# nixie-v-rev-b.net
KiCad netlist of a schematic drawn in EAGLE
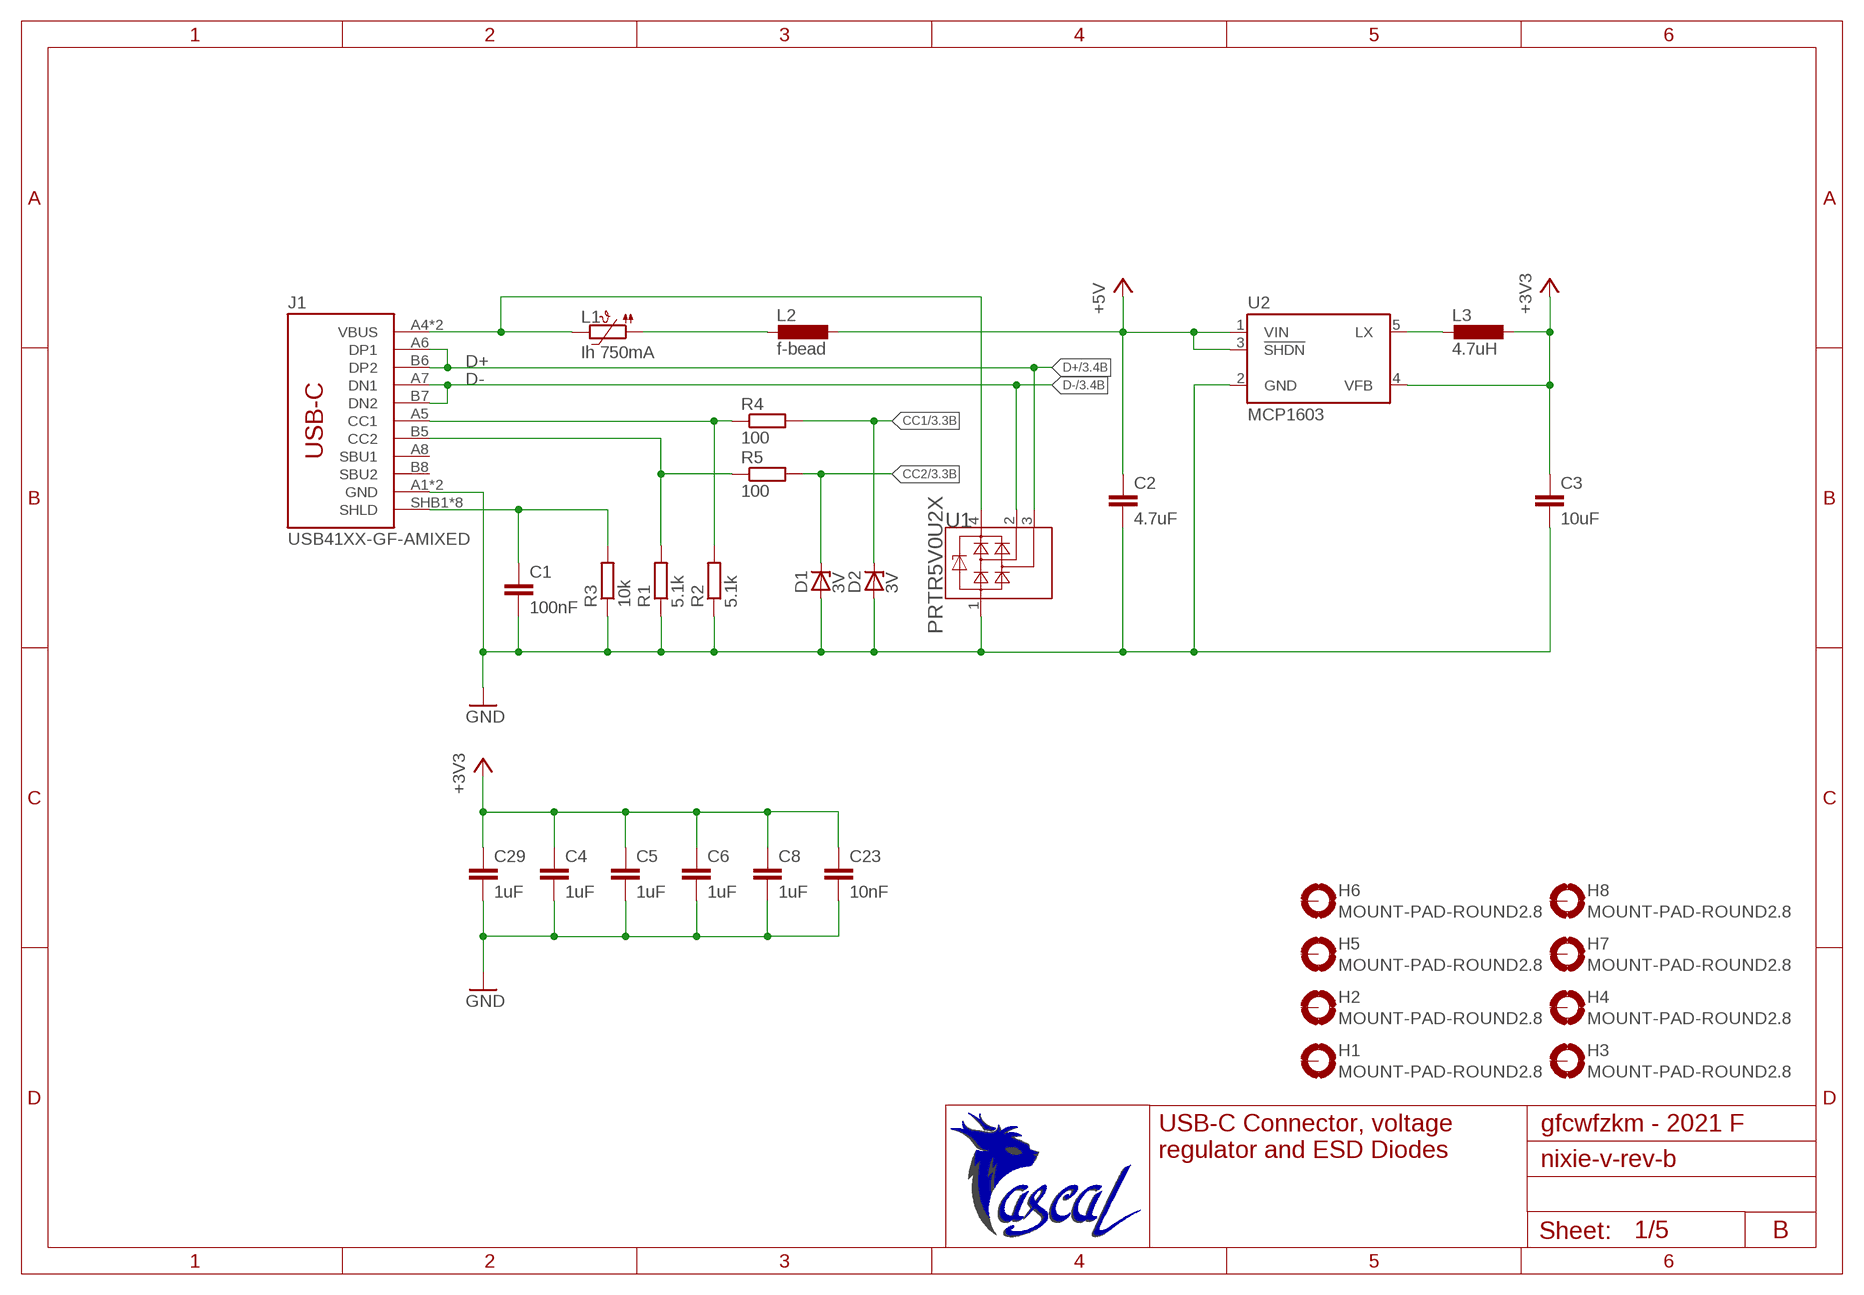
[diagram p0: schematic, sheet 1]
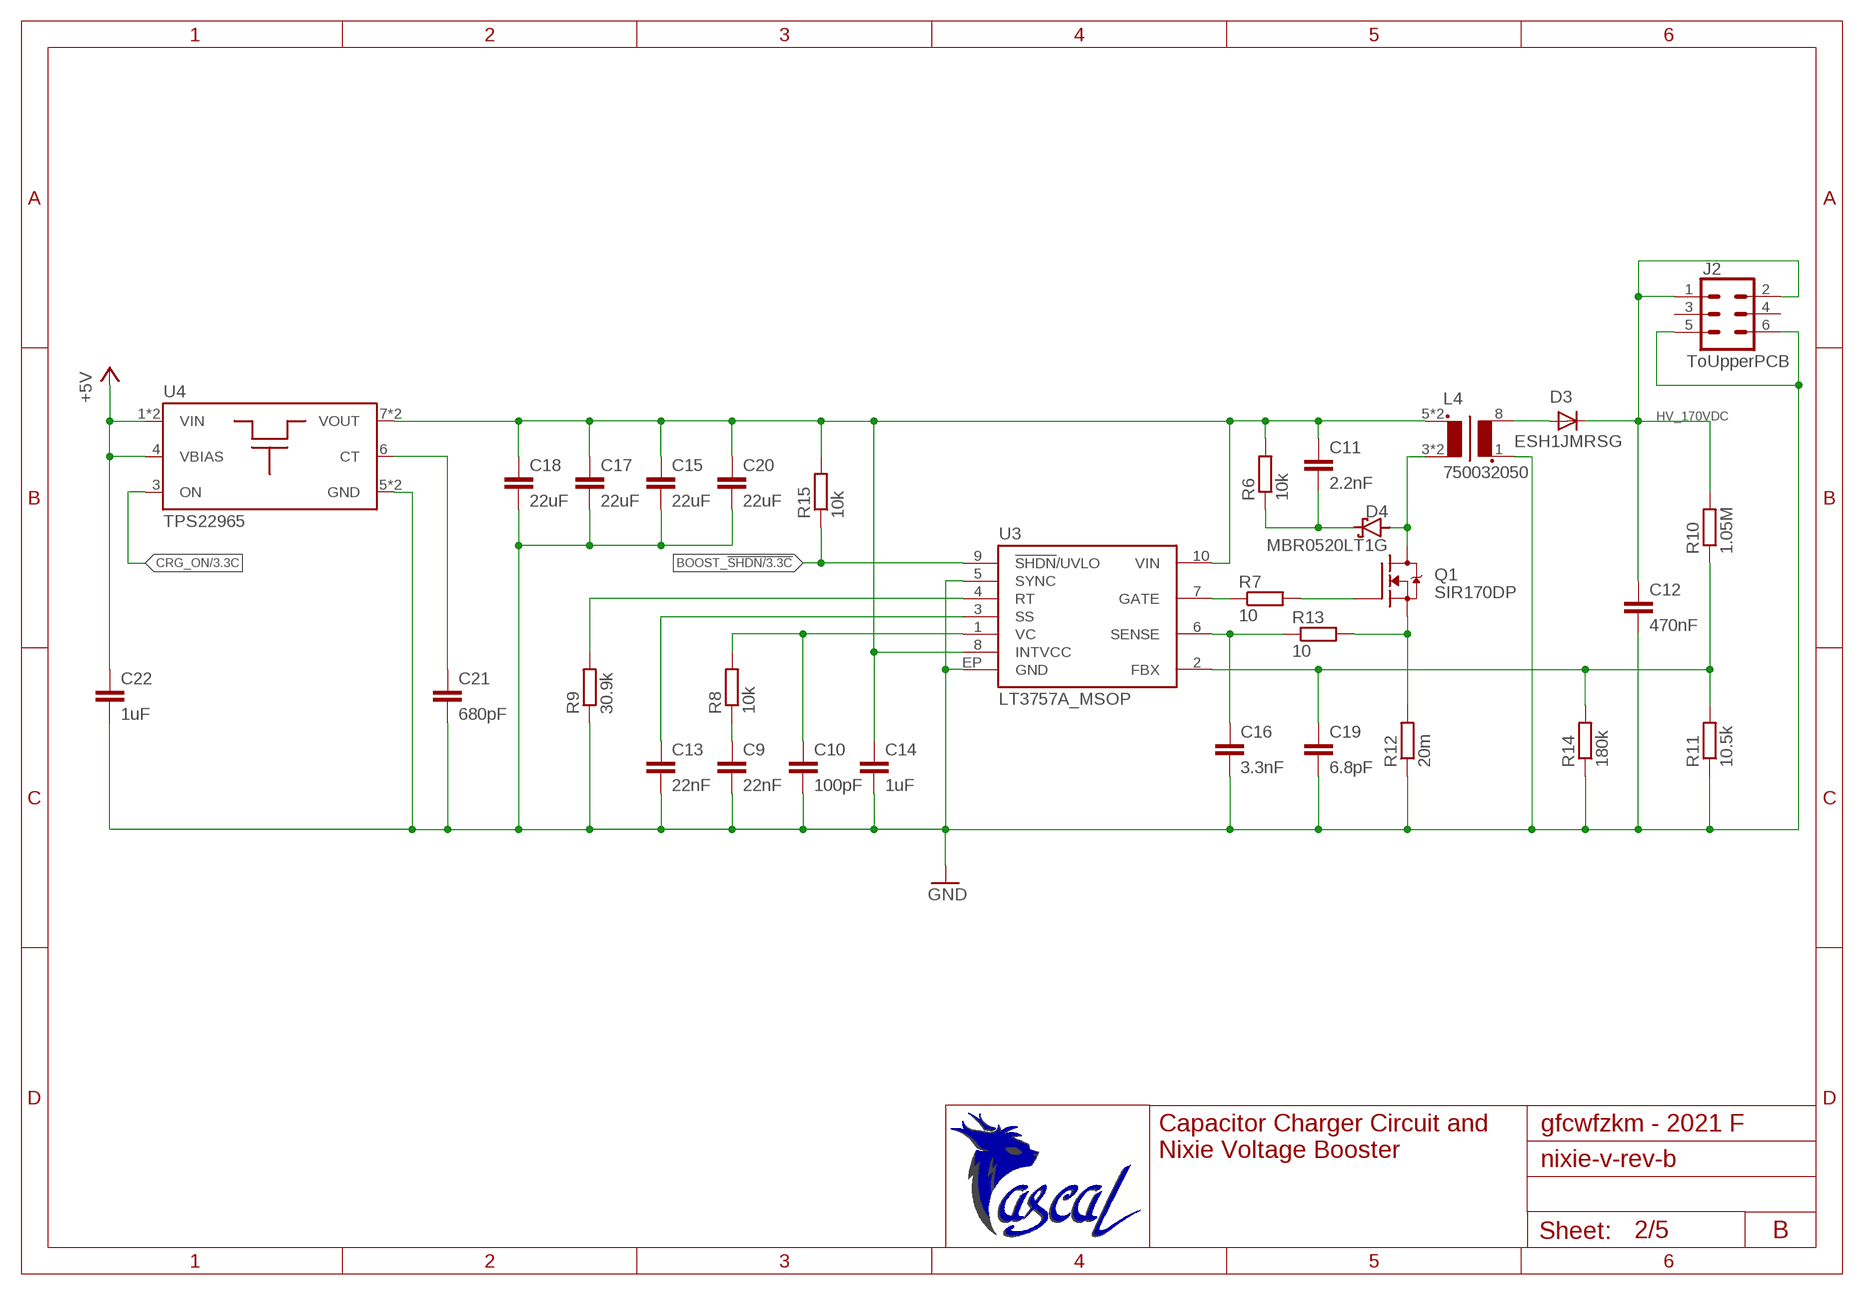
[diagram p1: schematic, sheet 2]
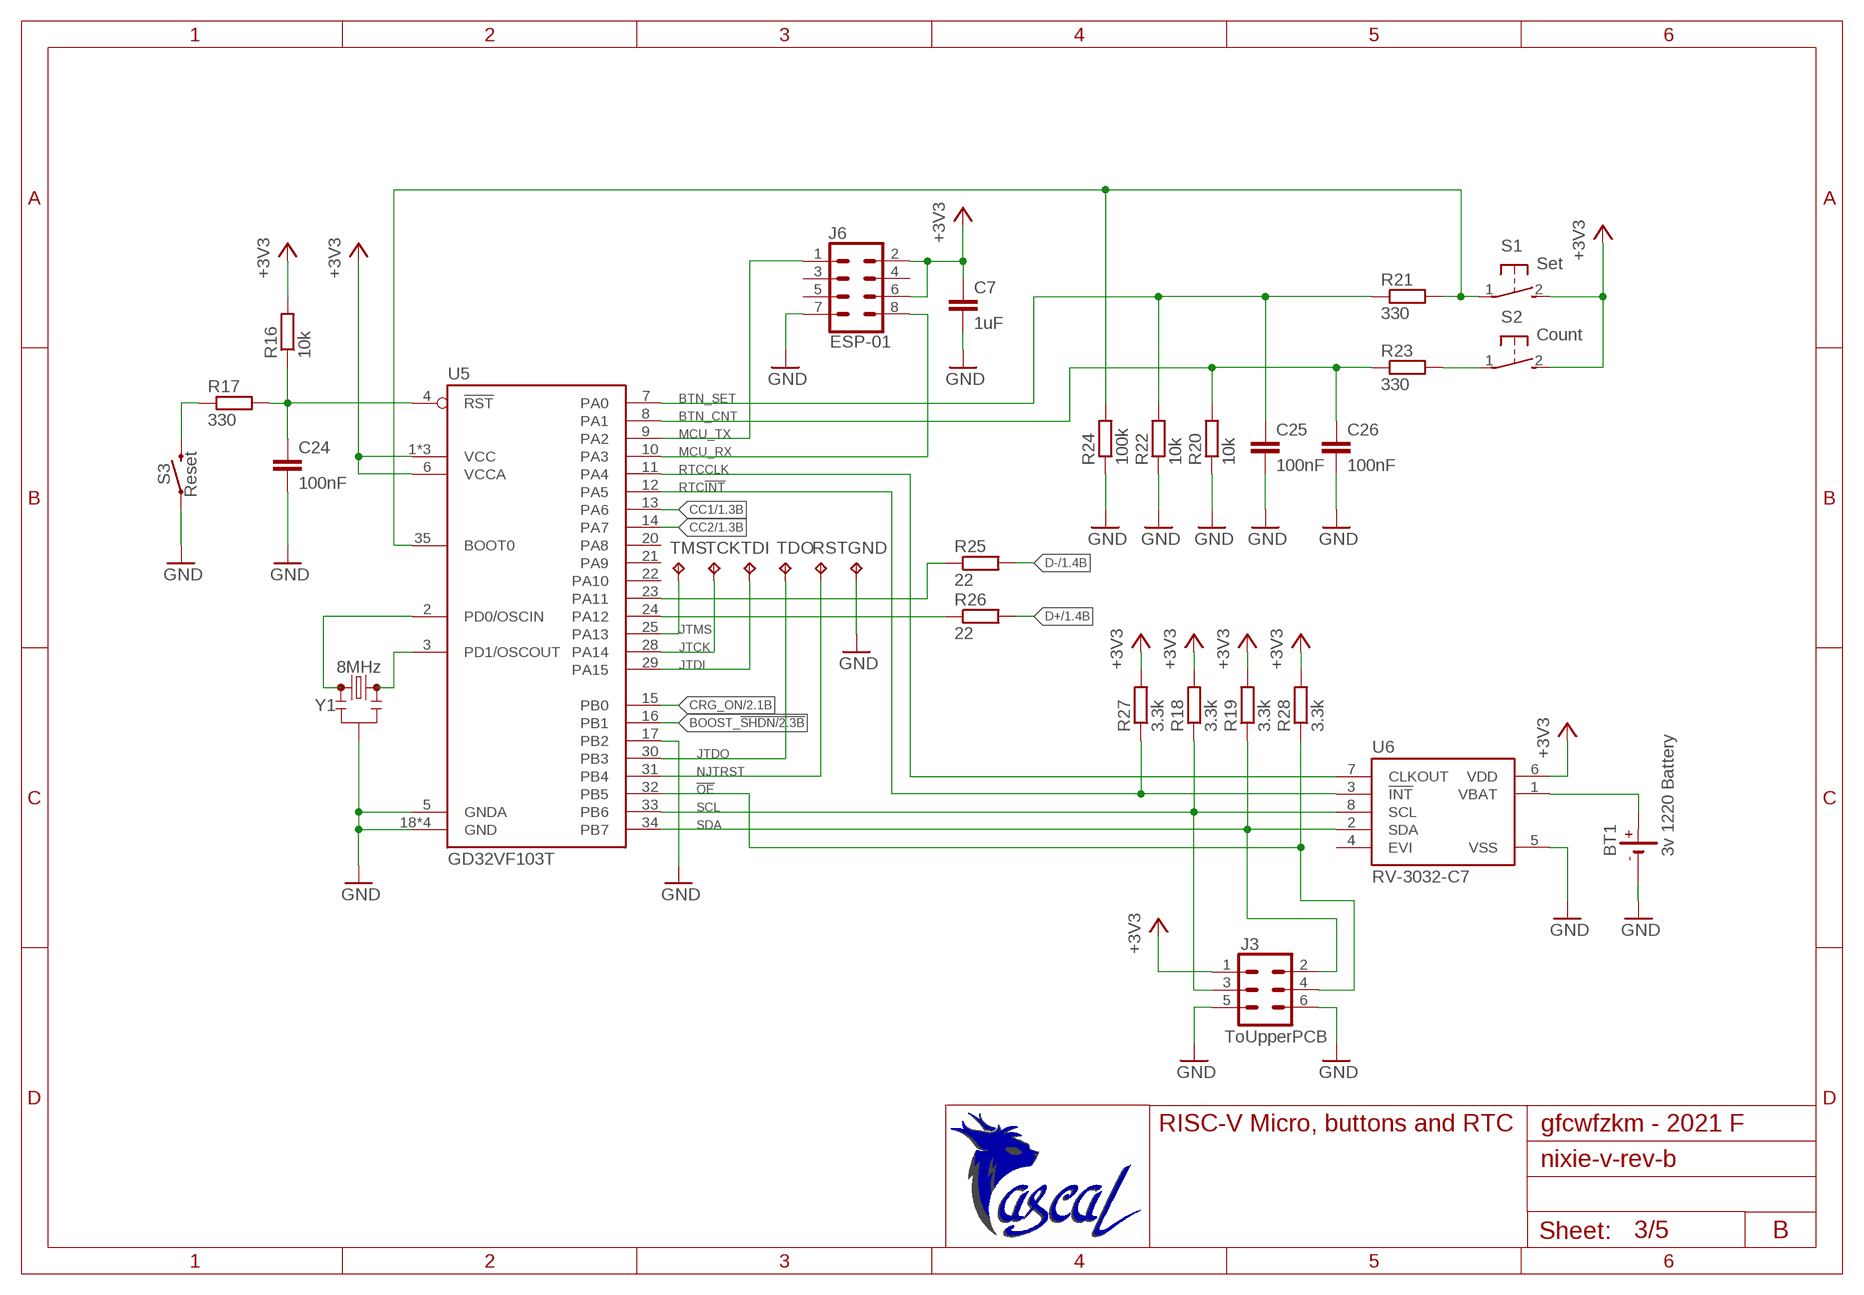
[diagram p2: schematic, sheet 3]
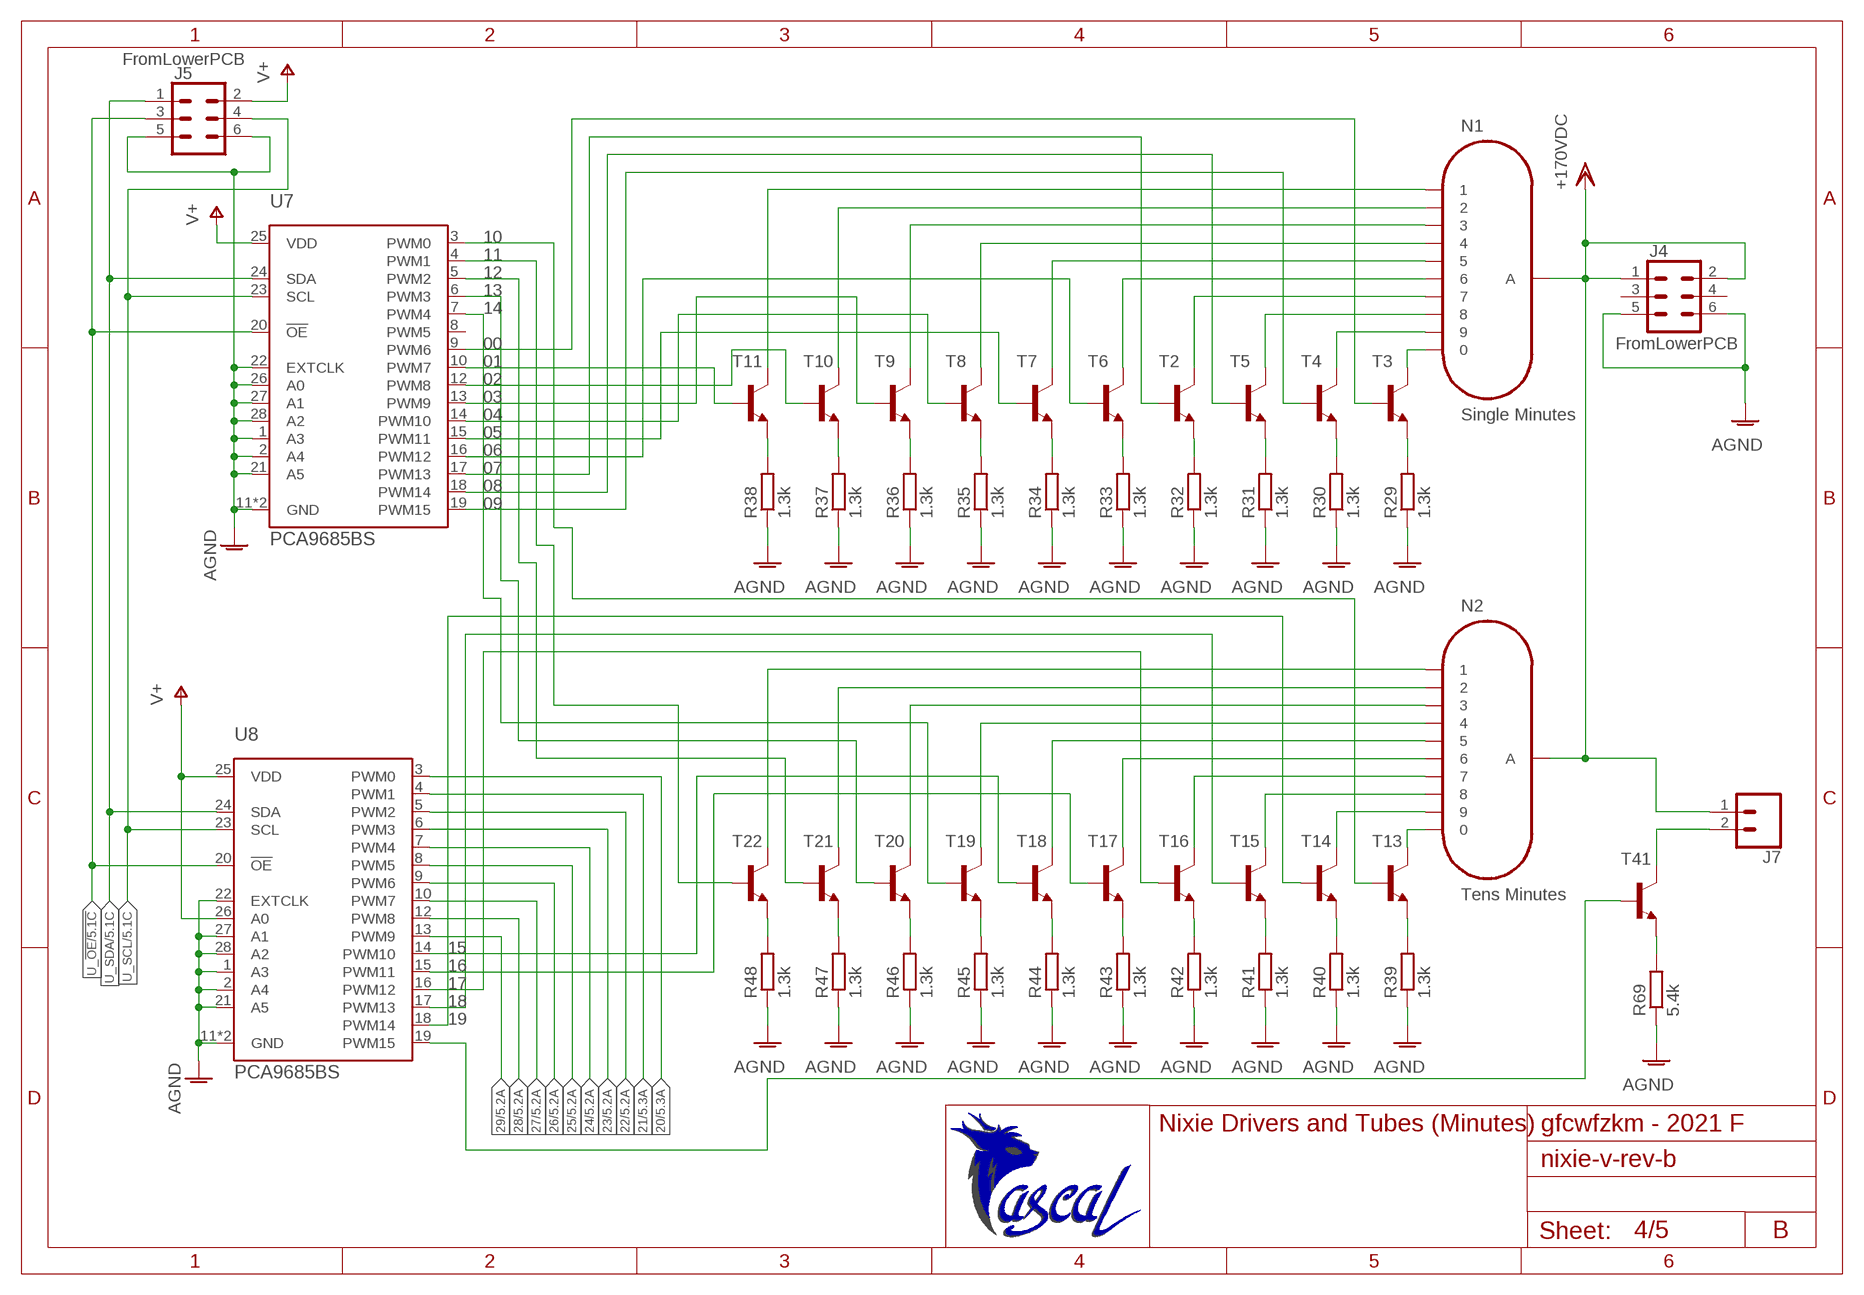
[diagram p3: schematic, sheet 4]
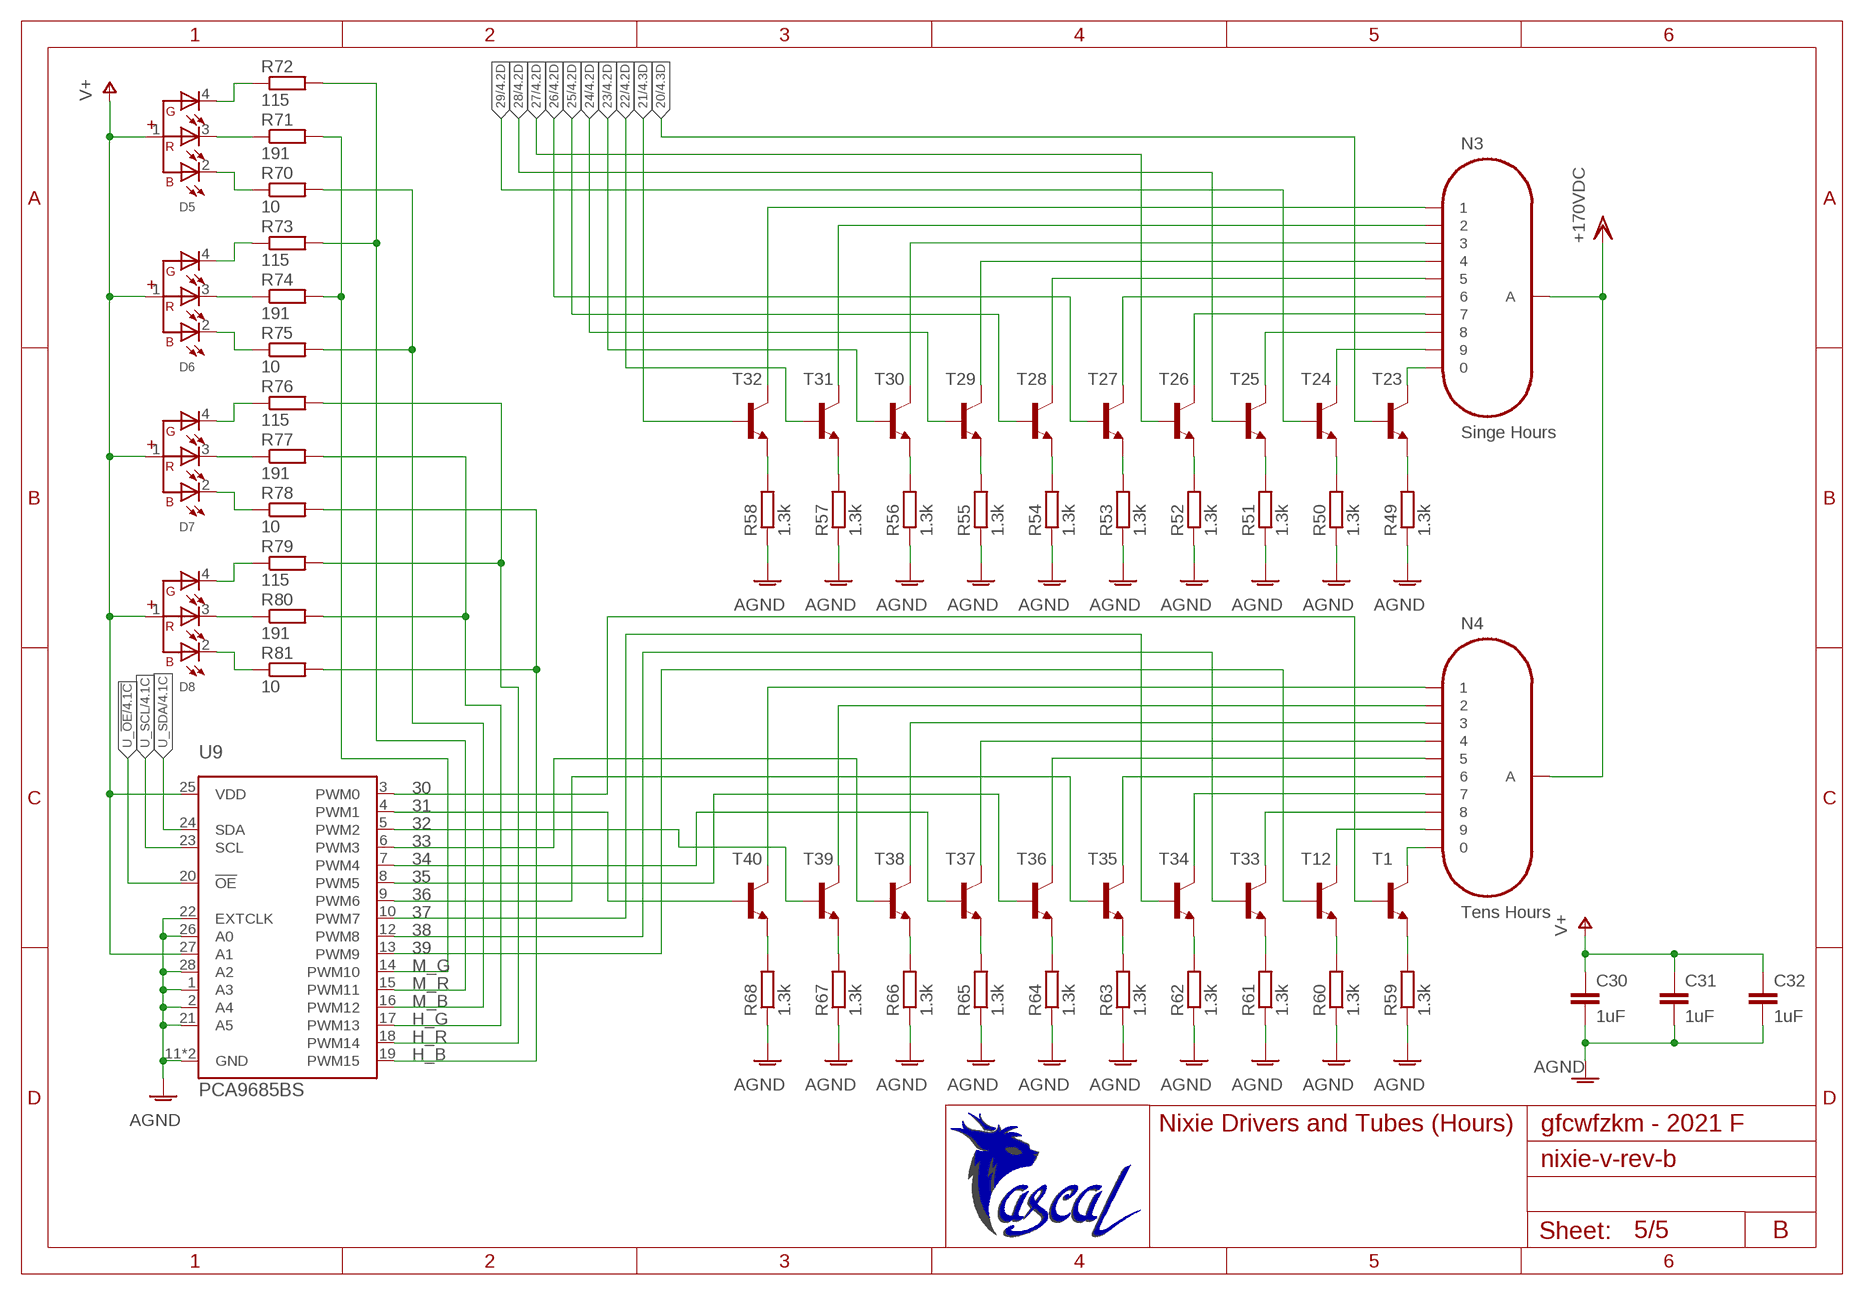
[diagram p4: schematic, sheet 5]

(export (version "E")
  (design (tool "Eeschema 10.0.6"))
  (components
    (comp (ref "J4")
      (value "FromLowerPCB")
      (footprint "eagle-import:2X3")
      (libsource (lib "eagle-import") (part "CONN_03X2FEMALE"))
    )
    (comp (ref "J5")
      (value "FromLowerPCB")
      (footprint "eagle-import:2X3")
      (libsource (lib "eagle-import") (part "CONN_03X2FEMALE"))
    )
    (comp (ref "J7")
      (value "CONN_02")
      (footprint "eagle-import:1X02")
      (libsource (lib "eagle-import") (part "CONN_02"))
    )
    (comp (ref "N1")
      (value "Single Minutes")
      (footprint "eagle-import:IN-8")
      (libsource (lib "eagle-import") (part "IN-8SMALL"))
    )
    (comp (ref "N2")
      (value "Tens Minutes")
      (footprint "eagle-import:IN-8")
      (libsource (lib "eagle-import") (part "IN-8SMALL"))
    )
    (comp (ref "R29")
      (value "1.3k")
      (footprint "eagle-import:R0603")
      (libsource (lib "eagle-import") (part "R-EU_R0603"))
    )
    (comp (ref "R30")
      (value "1.3k")
      (footprint "eagle-import:R0603")
      (libsource (lib "eagle-import") (part "R-EU_R0603"))
    )
    (comp (ref "R31")
      (value "1.3k")
      (footprint "eagle-import:R0603")
      (libsource (lib "eagle-import") (part "R-EU_R0603"))
    )
    (comp (ref "R32")
      (value "1.3k")
      (footprint "eagle-import:R0603")
      (libsource (lib "eagle-import") (part "R-EU_R0603"))
    )
    (comp (ref "R33")
      (value "1.3k")
      (footprint "eagle-import:R0603")
      (libsource (lib "eagle-import") (part "R-EU_R0603"))
    )
    (comp (ref "R34")
      (value "1.3k")
      (footprint "eagle-import:R0603")
      (libsource (lib "eagle-import") (part "R-EU_R0603"))
    )
    (comp (ref "R35")
      (value "1.3k")
      (footprint "eagle-import:R0603")
      (libsource (lib "eagle-import") (part "R-EU_R0603"))
    )
    (comp (ref "R36")
      (value "1.3k")
      (footprint "eagle-import:R0603")
      (libsource (lib "eagle-import") (part "R-EU_R0603"))
    )
    (comp (ref "R37")
      (value "1.3k")
      (footprint "eagle-import:R0603")
      (libsource (lib "eagle-import") (part "R-EU_R0603"))
    )
    (comp (ref "R38")
      (value "1.3k")
      (footprint "eagle-import:R0603")
      (libsource (lib "eagle-import") (part "R-EU_R0603"))
    )
    (comp (ref "R39")
      (value "1.3k")
      (footprint "eagle-import:R0603")
      (libsource (lib "eagle-import") (part "R-EU_R0603"))
    )
    (comp (ref "R40")
      (value "1.3k")
      (footprint "eagle-import:R0603")
      (libsource (lib "eagle-import") (part "R-EU_R0603"))
    )
    (comp (ref "R41")
      (value "1.3k")
      (footprint "eagle-import:R0603")
      (libsource (lib "eagle-import") (part "R-EU_R0603"))
    )
    (comp (ref "R42")
      (value "1.3k")
      (footprint "eagle-import:R0603")
      (libsource (lib "eagle-import") (part "R-EU_R0603"))
    )
    (comp (ref "R43")
      (value "1.3k")
      (footprint "eagle-import:R0603")
      (libsource (lib "eagle-import") (part "R-EU_R0603"))
    )
    (comp (ref "R44")
      (value "1.3k")
      (footprint "eagle-import:R0603")
      (libsource (lib "eagle-import") (part "R-EU_R0603"))
    )
    (comp (ref "R45")
      (value "1.3k")
      (footprint "eagle-import:R0603")
      (libsource (lib "eagle-import") (part "R-EU_R0603"))
    )
    (comp (ref "R46")
      (value "1.3k")
      (footprint "eagle-import:R0603")
      (libsource (lib "eagle-import") (part "R-EU_R0603"))
    )
    (comp (ref "R47")
      (value "1.3k")
      (footprint "eagle-import:R0603")
      (libsource (lib "eagle-import") (part "R-EU_R0603"))
    )
    (comp (ref "R48")
      (value "1.3k")
      (footprint "eagle-import:R0603")
      (libsource (lib "eagle-import") (part "R-EU_R0603"))
    )
    (comp (ref "R69")
      (value "5.4k")
      (footprint "eagle-import:R0603")
      (libsource (lib "eagle-import") (part "R-EU_R0603"))
    )
    (comp (ref "T2")
      (value "MSD42WT1G")
      (footprint "eagle-import:SC70-3-R")
      (libsource (lib "eagle-import") (part "MSD42WT1G"))
    )
    (comp (ref "T3")
      (value "MSD42WT1G")
      (footprint "eagle-import:SC70-3-R")
      (libsource (lib "eagle-import") (part "MSD42WT1G"))
    )
    (comp (ref "T4")
      (value "MSD42WT1G")
      (footprint "eagle-import:SC70-3-R")
      (libsource (lib "eagle-import") (part "MSD42WT1G"))
    )
    (comp (ref "T5")
      (value "MSD42WT1G")
      (footprint "eagle-import:SC70-3-R")
      (libsource (lib "eagle-import") (part "MSD42WT1G"))
    )
    (comp (ref "T6")
      (value "MSD42WT1G")
      (footprint "eagle-import:SC70-3-R")
      (libsource (lib "eagle-import") (part "MSD42WT1G"))
    )
    (comp (ref "T7")
      (value "MSD42WT1G")
      (footprint "eagle-import:SC70-3-R")
      (libsource (lib "eagle-import") (part "MSD42WT1G"))
    )
    (comp (ref "T8")
      (value "MSD42WT1G")
      (footprint "eagle-import:SC70-3-R")
      (libsource (lib "eagle-import") (part "MSD42WT1G"))
    )
    (comp (ref "T9")
      (value "MSD42WT1G")
      (footprint "eagle-import:SC70-3-R")
      (libsource (lib "eagle-import") (part "MSD42WT1G"))
    )
    (comp (ref "T10")
      (value "MSD42WT1G")
      (footprint "eagle-import:SC70-3-R")
      (libsource (lib "eagle-import") (part "MSD42WT1G"))
    )
    (comp (ref "T11")
      (value "MSD42WT1G")
      (footprint "eagle-import:SC70-3-R")
      (libsource (lib "eagle-import") (part "MSD42WT1G"))
    )
    (comp (ref "T13")
      (value "MSD42WT1G")
      (footprint "eagle-import:SC70-3-R")
      (libsource (lib "eagle-import") (part "MSD42WT1G"))
    )
    (comp (ref "T14")
      (value "MSD42WT1G")
      (footprint "eagle-import:SC70-3-R")
      (libsource (lib "eagle-import") (part "MSD42WT1G"))
    )
    (comp (ref "T15")
      (value "MSD42WT1G")
      (footprint "eagle-import:SC70-3-R")
      (libsource (lib "eagle-import") (part "MSD42WT1G"))
    )
    (comp (ref "T16")
      (value "MSD42WT1G")
      (footprint "eagle-import:SC70-3-R")
      (libsource (lib "eagle-import") (part "MSD42WT1G"))
    )
    (comp (ref "T17")
      (value "MSD42WT1G")
      (footprint "eagle-import:SC70-3-R")
      (libsource (lib "eagle-import") (part "MSD42WT1G"))
    )
    (comp (ref "T18")
      (value "MSD42WT1G")
      (footprint "eagle-import:SC70-3-R")
      (libsource (lib "eagle-import") (part "MSD42WT1G"))
    )
    (comp (ref "T19")
      (value "MSD42WT1G")
      (footprint "eagle-import:SC70-3-R")
      (libsource (lib "eagle-import") (part "MSD42WT1G"))
    )
    (comp (ref "T20")
      (value "MSD42WT1G")
      (footprint "eagle-import:SC70-3-R")
      (libsource (lib "eagle-import") (part "MSD42WT1G"))
    )
    (comp (ref "T21")
      (value "MSD42WT1G")
      (footprint "eagle-import:SC70-3-R")
      (libsource (lib "eagle-import") (part "MSD42WT1G"))
    )
    (comp (ref "T22")
      (value "MSD42WT1G")
      (footprint "eagle-import:SC70-3-R")
      (libsource (lib "eagle-import") (part "MSD42WT1G"))
    )
    (comp (ref "T41")
      (value "MSD42WT1G")
      (footprint "eagle-import:SC70-3-R")
      (libsource (lib "eagle-import") (part "MSD42WT1G"))
    )
    (comp (ref "U$4")
      (value "LOGO_PASCAL_GESELLEMPTY")
      (footprint "eagle-import:EMPTY")
      (libsource (lib "eagle-import") (part "LOGO_PASCAL_GESELLEMPTY"))
    )
    (comp (ref "U7")
      (value "PCA9685BS")
      (footprint "eagle-import:HVQFN28")
      (libsource (lib "eagle-import") (part "PCA9685BS"))
    )
    (comp (ref "U8")
      (value "PCA9685BS")
      (footprint "eagle-import:HVQFN28")
      (libsource (lib "eagle-import") (part "PCA9685BS"))
    )
    (comp (ref "C30")
      (value "1uF")
      (footprint "eagle-import:C0603")
      (libsource (lib "eagle-import") (part "C-EUC0603"))
    )
    (comp (ref "C31")
      (value "1uF")
      (footprint "eagle-import:C0603")
      (libsource (lib "eagle-import") (part "C-EUC0603"))
    )
    (comp (ref "C32")
      (value "1uF")
      (footprint "eagle-import:C0603")
      (libsource (lib "eagle-import") (part "C-EUC0603"))
    )
    (comp (ref "D5")
      (value "WL-SFRW_1206_REC_156120M173000_NOR")
      (footprint "eagle-import:WL-SFRW_1206_REC")
      (libsource (lib "eagle-import") (part "WL-SFRW_1206_REC_NOR_156120M173000"))
    )
    (comp (ref "D6")
      (value "WL-SFRW_1206_REC_156120M173000_NOR")
      (footprint "eagle-import:WL-SFRW_1206_REC")
      (libsource (lib "eagle-import") (part "WL-SFRW_1206_REC_NOR_156120M173000"))
    )
    (comp (ref "D7")
      (value "WL-SFRW_1206_REC_156120M173000_NOR")
      (footprint "eagle-import:WL-SFRW_1206_REC")
      (libsource (lib "eagle-import") (part "WL-SFRW_1206_REC_NOR_156120M173000"))
    )
    (comp (ref "D8")
      (value "WL-SFRW_1206_REC_156120M173000_NOR")
      (footprint "eagle-import:WL-SFRW_1206_REC")
      (libsource (lib "eagle-import") (part "WL-SFRW_1206_REC_NOR_156120M173000"))
    )
    (comp (ref "N3")
      (value "Singe Hours")
      (footprint "eagle-import:IN-8")
      (libsource (lib "eagle-import") (part "IN-8SMALL"))
    )
    (comp (ref "N4")
      (value "Tens Hours")
      (footprint "eagle-import:IN-8")
      (libsource (lib "eagle-import") (part "IN-8SMALL"))
    )
    (comp (ref "R49")
      (value "1.3k")
      (footprint "eagle-import:R0603")
      (libsource (lib "eagle-import") (part "R-EU_R0603"))
    )
    (comp (ref "R50")
      (value "1.3k")
      (footprint "eagle-import:R0603")
      (libsource (lib "eagle-import") (part "R-EU_R0603"))
    )
    (comp (ref "R51")
      (value "1.3k")
      (footprint "eagle-import:R0603")
      (libsource (lib "eagle-import") (part "R-EU_R0603"))
    )
    (comp (ref "R52")
      (value "1.3k")
      (footprint "eagle-import:R0603")
      (libsource (lib "eagle-import") (part "R-EU_R0603"))
    )
    (comp (ref "R53")
      (value "1.3k")
      (footprint "eagle-import:R0603")
      (libsource (lib "eagle-import") (part "R-EU_R0603"))
    )
    (comp (ref "R54")
      (value "1.3k")
      (footprint "eagle-import:R0603")
      (libsource (lib "eagle-import") (part "R-EU_R0603"))
    )
    (comp (ref "R55")
      (value "1.3k")
      (footprint "eagle-import:R0603")
      (libsource (lib "eagle-import") (part "R-EU_R0603"))
    )
    (comp (ref "R56")
      (value "1.3k")
      (footprint "eagle-import:R0603")
      (libsource (lib "eagle-import") (part "R-EU_R0603"))
    )
    (comp (ref "R57")
      (value "1.3k")
      (footprint "eagle-import:R0603")
      (libsource (lib "eagle-import") (part "R-EU_R0603"))
    )
    (comp (ref "R58")
      (value "1.3k")
      (footprint "eagle-import:R0603")
      (libsource (lib "eagle-import") (part "R-EU_R0603"))
    )
    (comp (ref "R59")
      (value "1.3k")
      (footprint "eagle-import:R0603")
      (libsource (lib "eagle-import") (part "R-EU_R0603"))
    )
    (comp (ref "R60")
      (value "1.3k")
      (footprint "eagle-import:R0603")
      (libsource (lib "eagle-import") (part "R-EU_R0603"))
    )
    (comp (ref "R61")
      (value "1.3k")
      (footprint "eagle-import:R0603")
      (libsource (lib "eagle-import") (part "R-EU_R0603"))
    )
    (comp (ref "R62")
      (value "1.3k")
      (footprint "eagle-import:R0603")
      (libsource (lib "eagle-import") (part "R-EU_R0603"))
    )
    (comp (ref "R63")
      (value "1.3k")
      (footprint "eagle-import:R0603")
      (libsource (lib "eagle-import") (part "R-EU_R0603"))
    )
    (comp (ref "R64")
      (value "1.3k")
      (footprint "eagle-import:R0603")
      (libsource (lib "eagle-import") (part "R-EU_R0603"))
    )
    (comp (ref "R65")
      (value "1.3k")
      (footprint "eagle-import:R0603")
      (libsource (lib "eagle-import") (part "R-EU_R0603"))
    )
    (comp (ref "R66")
      (value "1.3k")
      (footprint "eagle-import:R0603")
      (libsource (lib "eagle-import") (part "R-EU_R0603"))
    )
    (comp (ref "R67")
      (value "1.3k")
      (footprint "eagle-import:R0603")
      (libsource (lib "eagle-import") (part "R-EU_R0603"))
    )
    (comp (ref "R68")
      (value "1.3k")
      (footprint "eagle-import:R0603")
      (libsource (lib "eagle-import") (part "R-EU_R0603"))
    )
    (comp (ref "R70")
      (value "10")
      (footprint "eagle-import:R0603")
      (libsource (lib "eagle-import") (part "R-EU_R0603"))
    )
    (comp (ref "R71")
      (value "191")
      (footprint "eagle-import:R0603")
      (libsource (lib "eagle-import") (part "R-EU_R0603"))
    )
    (comp (ref "R72")
      (value "115")
      (footprint "eagle-import:R0603")
      (libsource (lib "eagle-import") (part "R-EU_R0603"))
    )
    (comp (ref "R73")
      (value "115")
      (footprint "eagle-import:R0603")
      (libsource (lib "eagle-import") (part "R-EU_R0603"))
    )
    (comp (ref "R74")
      (value "191")
      (footprint "eagle-import:R0603")
      (libsource (lib "eagle-import") (part "R-EU_R0603"))
    )
    (comp (ref "R75")
      (value "10")
      (footprint "eagle-import:R0603")
      (libsource (lib "eagle-import") (part "R-EU_R0603"))
    )
    (comp (ref "R76")
      (value "115")
      (footprint "eagle-import:R0603")
      (libsource (lib "eagle-import") (part "R-EU_R0603"))
    )
    (comp (ref "R77")
      (value "191")
      (footprint "eagle-import:R0603")
      (libsource (lib "eagle-import") (part "R-EU_R0603"))
    )
    (comp (ref "R78")
      (value "10")
      (footprint "eagle-import:R0603")
      (libsource (lib "eagle-import") (part "R-EU_R0603"))
    )
    (comp (ref "R79")
      (value "115")
      (footprint "eagle-import:R0603")
      (libsource (lib "eagle-import") (part "R-EU_R0603"))
    )
    (comp (ref "R80")
      (value "191")
      (footprint "eagle-import:R0603")
      (libsource (lib "eagle-import") (part "R-EU_R0603"))
    )
    (comp (ref "R81")
      (value "10")
      (footprint "eagle-import:R0603")
      (libsource (lib "eagle-import") (part "R-EU_R0603"))
    )
    (comp (ref "T1")
      (value "MSD42WT1G")
      (footprint "eagle-import:SC70-3-R")
      (libsource (lib "eagle-import") (part "MSD42WT1G"))
    )
    (comp (ref "T12")
      (value "MSD42WT1G")
      (footprint "eagle-import:SC70-3-R")
      (libsource (lib "eagle-import") (part "MSD42WT1G"))
    )
    (comp (ref "T23")
      (value "MSD42WT1G")
      (footprint "eagle-import:SC70-3-R")
      (libsource (lib "eagle-import") (part "MSD42WT1G"))
    )
    (comp (ref "T24")
      (value "MSD42WT1G")
      (footprint "eagle-import:SC70-3-R")
      (libsource (lib "eagle-import") (part "MSD42WT1G"))
    )
    (comp (ref "T25")
      (value "MSD42WT1G")
      (footprint "eagle-import:SC70-3-R")
      (libsource (lib "eagle-import") (part "MSD42WT1G"))
    )
    (comp (ref "T26")
      (value "MSD42WT1G")
      (footprint "eagle-import:SC70-3-R")
      (libsource (lib "eagle-import") (part "MSD42WT1G"))
    )
    (comp (ref "T27")
      (value "MSD42WT1G")
      (footprint "eagle-import:SC70-3-R")
      (libsource (lib "eagle-import") (part "MSD42WT1G"))
    )
    (comp (ref "T28")
      (value "MSD42WT1G")
      (footprint "eagle-import:SC70-3-R")
      (libsource (lib "eagle-import") (part "MSD42WT1G"))
    )
    (comp (ref "T29")
      (value "MSD42WT1G")
      (footprint "eagle-import:SC70-3-R")
      (libsource (lib "eagle-import") (part "MSD42WT1G"))
    )
    (comp (ref "T30")
      (value "MSD42WT1G")
      (footprint "eagle-import:SC70-3-R")
      (libsource (lib "eagle-import") (part "MSD42WT1G"))
    )
    (comp (ref "T31")
      (value "MSD42WT1G")
      (footprint "eagle-import:SC70-3-R")
      (libsource (lib "eagle-import") (part "MSD42WT1G"))
    )
    (comp (ref "T32")
      (value "MSD42WT1G")
      (footprint "eagle-import:SC70-3-R")
      (libsource (lib "eagle-import") (part "MSD42WT1G"))
    )
    (comp (ref "T33")
      (value "MSD42WT1G")
      (footprint "eagle-import:SC70-3-R")
      (libsource (lib "eagle-import") (part "MSD42WT1G"))
    )
    (comp (ref "T34")
      (value "MSD42WT1G")
      (footprint "eagle-import:SC70-3-R")
      (libsource (lib "eagle-import") (part "MSD42WT1G"))
    )
    (comp (ref "T35")
      (value "MSD42WT1G")
      (footprint "eagle-import:SC70-3-R")
      (libsource (lib "eagle-import") (part "MSD42WT1G"))
    )
    (comp (ref "T36")
      (value "MSD42WT1G")
      (footprint "eagle-import:SC70-3-R")
      (libsource (lib "eagle-import") (part "MSD42WT1G"))
    )
    (comp (ref "T37")
      (value "MSD42WT1G")
      (footprint "eagle-import:SC70-3-R")
      (libsource (lib "eagle-import") (part "MSD42WT1G"))
    )
    (comp (ref "T38")
      (value "MSD42WT1G")
      (footprint "eagle-import:SC70-3-R")
      (libsource (lib "eagle-import") (part "MSD42WT1G"))
    )
    (comp (ref "T39")
      (value "MSD42WT1G")
      (footprint "eagle-import:SC70-3-R")
      (libsource (lib "eagle-import") (part "MSD42WT1G"))
    )
    (comp (ref "T40")
      (value "MSD42WT1G")
      (footprint "eagle-import:SC70-3-R")
      (libsource (lib "eagle-import") (part "MSD42WT1G"))
    )
    (comp (ref "U$5")
      (value "LOGO_PASCAL_GESELLEMPTY")
      (footprint "eagle-import:EMPTY")
      (libsource (lib "eagle-import") (part "LOGO_PASCAL_GESELLEMPTY"))
    )
    (comp (ref "U9")
      (value "PCA9685BS")
      (footprint "eagle-import:HVQFN28")
      (libsource (lib "eagle-import") (part "PCA9685BS"))
    )
    (comp (ref "C1")
      (value "100nF")
      (footprint "eagle-import:C0603")
      (libsource (lib "eagle-import") (part "C-EUC0603"))
    )
    (comp (ref "C2")
      (value "4.7uF")
      (footprint "eagle-import:C0805")
      (libsource (lib "eagle-import") (part "C-EUC0805"))
    )
    (comp (ref "C3")
      (value "10uF")
      (footprint "eagle-import:C0805")
      (libsource (lib "eagle-import") (part "C-EUC0805"))
    )
    (comp (ref "C4")
      (value "1uF")
      (footprint "eagle-import:C0603")
      (libsource (lib "eagle-import") (part "C-EUC0603"))
    )
    (comp (ref "C5")
      (value "1uF")
      (footprint "eagle-import:C0603")
      (libsource (lib "eagle-import") (part "C-EUC0603"))
    )
    (comp (ref "C6")
      (value "1uF")
      (footprint "eagle-import:C0603")
      (libsource (lib "eagle-import") (part "C-EUC0603"))
    )
    (comp (ref "C8")
      (value "1uF")
      (footprint "eagle-import:C0603")
      (libsource (lib "eagle-import") (part "C-EUC0603"))
    )
    (comp (ref "C23")
      (value "10nF")
      (footprint "eagle-import:C0603")
      (libsource (lib "eagle-import") (part "C-EUC0603"))
    )
    (comp (ref "C29")
      (value "1uF")
      (footprint "eagle-import:C0603")
      (libsource (lib "eagle-import") (part "C-EUC0603"))
    )
    (comp (ref "D1")
      (value "3V")
      (footprint "eagle-import:SOD-523")
      (libsource (lib "eagle-import") (part "VESD05A1-02V-G3-08"))
    )
    (comp (ref "D2")
      (value "3V")
      (footprint "eagle-import:SOD-523")
      (libsource (lib "eagle-import") (part "VESD05A1-02V-G3-08"))
    )
    (comp (ref "H1")
      (value "MOUNT-PAD-ROUND2.8")
      (footprint "eagle-import:2,8-PAD")
      (libsource (lib "eagle-import") (part "MOUNT-PAD-ROUND2.8"))
    )
    (comp (ref "H2")
      (value "MOUNT-PAD-ROUND2.8")
      (footprint "eagle-import:2,8-PAD")
      (libsource (lib "eagle-import") (part "MOUNT-PAD-ROUND2.8"))
    )
    (comp (ref "H3")
      (value "MOUNT-PAD-ROUND2.8")
      (footprint "eagle-import:2,8-PAD")
      (libsource (lib "eagle-import") (part "MOUNT-PAD-ROUND2.8"))
    )
    (comp (ref "H4")
      (value "MOUNT-PAD-ROUND2.8")
      (footprint "eagle-import:2,8-PAD")
      (libsource (lib "eagle-import") (part "MOUNT-PAD-ROUND2.8"))
    )
    (comp (ref "H5")
      (value "MOUNT-PAD-ROUND2.8")
      (footprint "eagle-import:2,8-PAD")
      (libsource (lib "eagle-import") (part "MOUNT-PAD-ROUND2.8"))
    )
    (comp (ref "H6")
      (value "MOUNT-PAD-ROUND2.8")
      (footprint "eagle-import:2,8-PAD")
      (libsource (lib "eagle-import") (part "MOUNT-PAD-ROUND2.8"))
    )
    (comp (ref "H7")
      (value "MOUNT-PAD-ROUND2.8")
      (footprint "eagle-import:2,8-PAD")
      (libsource (lib "eagle-import") (part "MOUNT-PAD-ROUND2.8"))
    )
    (comp (ref "H8")
      (value "MOUNT-PAD-ROUND2.8")
      (footprint "eagle-import:2,8-PAD")
      (libsource (lib "eagle-import") (part "MOUNT-PAD-ROUND2.8"))
    )
    (comp (ref "J1")
      (value "USB41XX-GF-AMIXED")
      (footprint "eagle-import:USB4105-GF-A")
      (libsource (lib "eagle-import") (part "USB41XX-GF-AMIXED"))
    )
    (comp (ref "L1")
      (value "Ih 750mA")
      (footprint "eagle-import:R0805")
      (libsource (lib "eagle-import") (part "PTC_FUSE0805"))
    )
    (comp (ref "L2")
      (value "f-bead")
      (footprint "eagle-import:R0805")
      (libsource (lib "eagle-import") (part "L-COIL"))
    )
    (comp (ref "L3")
      (value "4.7uH")
      (footprint "eagle-import:R1210")
      (libsource (lib "eagle-import") (part "L1210"))
    )
    (comp (ref "R1")
      (value "5.1k")
      (footprint "eagle-import:R0603")
      (libsource (lib "eagle-import") (part "R-EU_R0603"))
    )
    (comp (ref "R2")
      (value "5.1k")
      (footprint "eagle-import:R0603")
      (libsource (lib "eagle-import") (part "R-EU_R0603"))
    )
    (comp (ref "R3")
      (value "10k")
      (footprint "eagle-import:R0603")
      (libsource (lib "eagle-import") (part "R-EU_R0603"))
    )
    (comp (ref "R4")
      (value "100")
      (footprint "eagle-import:R0603")
      (libsource (lib "eagle-import") (part "R-EU_R0603"))
    )
    (comp (ref "R5")
      (value "100")
      (footprint "eagle-import:R0603")
      (libsource (lib "eagle-import") (part "R-EU_R0603"))
    )
    (comp (ref "U$1")
      (value "LOGO_PASCAL_GESELL30MM")
      (footprint "eagle-import:LOGO_30MM")
      (libsource (lib "eagle-import") (part "LOGO_PASCAL_GESELL30MM"))
    )
    (comp (ref "U1")
      (value "PRTR5V0U2X")
      (footprint "eagle-import:SOT143B")
      (libsource (lib "eagle-import") (part "PRTR5V0U2X"))
    )
    (comp (ref "U2")
      (value "MCP1603")
      (footprint "eagle-import:TSOT23-5")
      (libsource (lib "eagle-import") (part "MCP1603"))
    )
    (comp (ref "C9")
      (value "22nF")
      (footprint "eagle-import:C0603")
      (libsource (lib "eagle-import") (part "C-EUC0603"))
    )
    (comp (ref "C10")
      (value "100pF")
      (footprint "eagle-import:C0603")
      (libsource (lib "eagle-import") (part "C-EUC0603"))
    )
    (comp (ref "C11")
      (value "2.2nF")
      (footprint "eagle-import:C0603")
      (libsource (lib "eagle-import") (part "C-EUC0603"))
    )
    (comp (ref "C12")
      (value "470nF")
      (footprint "eagle-import:C1812")
      (libsource (lib "eagle-import") (part "C-EUC1812"))
    )
    (comp (ref "C13")
      (value "22nF")
      (footprint "eagle-import:C0603")
      (libsource (lib "eagle-import") (part "C-EUC0603"))
    )
    (comp (ref "C14")
      (value "1uF")
      (footprint "eagle-import:C0603")
      (libsource (lib "eagle-import") (part "C-EUC0603"))
    )
    (comp (ref "C15")
      (value "22uF")
      (footprint "eagle-import:C0805")
      (libsource (lib "eagle-import") (part "C-EUC0805"))
    )
    (comp (ref "C16")
      (value "3.3nF")
      (footprint "eagle-import:C0603")
      (libsource (lib "eagle-import") (part "C-EUC0603"))
    )
    (comp (ref "C17")
      (value "22uF")
      (footprint "eagle-import:C0805")
      (libsource (lib "eagle-import") (part "C-EUC0805"))
    )
    (comp (ref "C18")
      (value "22uF")
      (footprint "eagle-import:C0805")
      (libsource (lib "eagle-import") (part "C-EUC0805"))
    )
    (comp (ref "C19")
      (value "6.8pF")
      (footprint "eagle-import:C0603")
      (libsource (lib "eagle-import") (part "C-EUC0603"))
    )
    (comp (ref "C20")
      (value "22uF")
      (footprint "eagle-import:C0805")
      (libsource (lib "eagle-import") (part "C-EUC0805"))
    )
    (comp (ref "C21")
      (value "680pF")
      (footprint "eagle-import:C0603")
      (libsource (lib "eagle-import") (part "C-EUC0603"))
    )
    (comp (ref "C22")
      (value "1uF")
      (footprint "eagle-import:C0603")
      (libsource (lib "eagle-import") (part "C-EUC0603"))
    )
    (comp (ref "D3")
      (value "ESH1JMRSG")
      (footprint "eagle-import:MICROSMA")
      (libsource (lib "eagle-import") (part "ESH1JMRSG"))
    )
    (comp (ref "D4")
      (value "MBR0520LT1G")
      (footprint "eagle-import:SOD-123")
      (fields
        (field (name "DIGIKEY_PART_NUMBER") "MBR0520LT1GOSTR-ND")
        (field (name "MANUFACTURER") "ON Semiconductor")
        (field (name "CREATED_BY") "PCBLayout.com")
      )
      (libsource (lib "eagle-import") (part "MBR0520LT1G"))
    )
    (comp (ref "J2")
      (value "ToUpperPCB")
      (footprint "eagle-import:2X3")
      (libsource (lib "eagle-import") (part "CONN_03X2FEMALE"))
    )
    (comp (ref "L4")
      (value "750032050")
      (footprint "eagle-import:750032050")
      (libsource (lib "eagle-import") (part "750032050"))
    )
    (comp (ref "Q1")
      (value "SIR170DP")
      (footprint "eagle-import:SO-08_POWERPAK")
      (libsource (lib "eagle-import") (part "SIRA36DP"))
    )
    (comp (ref "R6")
      (value "10k")
      (footprint "eagle-import:R0603")
      (libsource (lib "eagle-import") (part "R-EU_R0603"))
    )
    (comp (ref "R7")
      (value "10")
      (footprint "eagle-import:R0603")
      (libsource (lib "eagle-import") (part "R-EU_R0603"))
    )
    (comp (ref "R8")
      (value "10k")
      (footprint "eagle-import:R0603")
      (libsource (lib "eagle-import") (part "R-EU_R0603"))
    )
    (comp (ref "R9")
      (value "30.9k")
      (footprint "eagle-import:R0603")
      (libsource (lib "eagle-import") (part "R-EU_R0603"))
    )
    (comp (ref "R10")
      (value "1.05M")
      (footprint "eagle-import:R0603")
      (libsource (lib "eagle-import") (part "R-EU_R0603"))
    )
    (comp (ref "R11")
      (value "10.5k")
      (footprint "eagle-import:R0603")
      (libsource (lib "eagle-import") (part "R-EU_R0603"))
    )
    (comp (ref "R12")
      (value "20m")
      (footprint "eagle-import:R0805")
      (libsource (lib "eagle-import") (part "R-EU_R0805"))
    )
    (comp (ref "R13")
      (value "10")
      (footprint "eagle-import:R0603")
      (libsource (lib "eagle-import") (part "R-EU_R0603"))
    )
    (comp (ref "R14")
      (value "180k")
      (footprint "eagle-import:R0603")
      (libsource (lib "eagle-import") (part "R-EU_R0603"))
    )
    (comp (ref "R15")
      (value "10k")
      (footprint "eagle-import:R0603")
      (libsource (lib "eagle-import") (part "R-EU_R0603"))
    )
    (comp (ref "U$2")
      (value "LOGO_PASCAL_GESELLEMPTY")
      (footprint "eagle-import:EMPTY")
      (libsource (lib "eagle-import") (part "LOGO_PASCAL_GESELLEMPTY"))
    )
    (comp (ref "U3")
      (value "LT3757A_MSOP")
      (footprint "eagle-import:MSOP10_POWER")
      (libsource (lib "eagle-import") (part "LT3757A_MSOP"))
    )
    (comp (ref "U4")
      (value "TPS22965")
      (footprint "eagle-import:WSON-8")
      (libsource (lib "eagle-import") (part "TPS22965"))
    )
    (comp (ref "BT1")
      (value "3v 1220 Battery")
      (footprint "eagle-import:CH291-1220LF")
      (libsource (lib "eagle-import") (part "BATTERY1056_KEYSTONE"))
    )
    (comp (ref "C7")
      (value "1uF")
      (footprint "eagle-import:C0603")
      (libsource (lib "eagle-import") (part "C-EUC0603"))
    )
    (comp (ref "C24")
      (value "100nF")
      (footprint "eagle-import:C0603")
      (libsource (lib "eagle-import") (part "C-EUC0603"))
    )
    (comp (ref "C25")
      (value "100nF")
      (footprint "eagle-import:C0603")
      (libsource (lib "eagle-import") (part "C-EUC0603"))
    )
    (comp (ref "C26")
      (value "100nF")
      (footprint "eagle-import:C0603")
      (libsource (lib "eagle-import") (part "C-EUC0603"))
    )
    (comp (ref "GND")
      (value "TPB1,27")
      (footprint "eagle-import:B1,27")
      (libsource (lib "eagle-import") (part "TPB1,27"))
    )
    (comp (ref "J3")
      (value "ToUpperPCB")
      (footprint "eagle-import:2X3")
      (libsource (lib "eagle-import") (part "CONN_03X2FEMALE"))
    )
    (comp (ref "J6")
      (value "ESP-01")
      (footprint "eagle-import:2X4")
      (libsource (lib "eagle-import") (part "CONN_04X2"))
    )
    (comp (ref "R16")
      (value "10k")
      (footprint "eagle-import:R0603")
      (libsource (lib "eagle-import") (part "R-EU_R0603"))
    )
    (comp (ref "R17")
      (value "330")
      (footprint "eagle-import:R0603")
      (libsource (lib "eagle-import") (part "R-EU_R0603"))
    )
    (comp (ref "R18")
      (value "3.3k")
      (footprint "eagle-import:R0603")
      (libsource (lib "eagle-import") (part "R-EU_R0603"))
    )
    (comp (ref "R19")
      (value "3.3k")
      (footprint "eagle-import:R0603")
      (libsource (lib "eagle-import") (part "R-EU_R0603"))
    )
    (comp (ref "R20")
      (value "10k")
      (footprint "eagle-import:R0603")
      (libsource (lib "eagle-import") (part "R-EU_R0603"))
    )
    (comp (ref "R21")
      (value "330")
      (footprint "eagle-import:R0603")
      (libsource (lib "eagle-import") (part "R-EU_R0603"))
    )
    (comp (ref "R22")
      (value "10k")
      (footprint "eagle-import:R0603")
      (libsource (lib "eagle-import") (part "R-EU_R0603"))
    )
    (comp (ref "R23")
      (value "330")
      (footprint "eagle-import:R0603")
      (libsource (lib "eagle-import") (part "R-EU_R0603"))
    )
    (comp (ref "R24")
      (value "100k")
      (footprint "eagle-import:R0603")
      (libsource (lib "eagle-import") (part "R-EU_R0603"))
    )
    (comp (ref "R25")
      (value "22")
      (footprint "eagle-import:R0603")
      (libsource (lib "eagle-import") (part "R-EU_R0603"))
    )
    (comp (ref "R26")
      (value "22")
      (footprint "eagle-import:R0603")
      (libsource (lib "eagle-import") (part "R-EU_R0603"))
    )
    (comp (ref "R27")
      (value "3.3k")
      (footprint "eagle-import:R0603")
      (libsource (lib "eagle-import") (part "R-EU_R0603"))
    )
    (comp (ref "R28")
      (value "3.3k")
      (footprint "eagle-import:R0603")
      (libsource (lib "eagle-import") (part "R-EU_R0603"))
    )
    (comp (ref "RST")
      (value "TPB1,27")
      (footprint "eagle-import:B1,27")
      (libsource (lib "eagle-import") (part "TPB1,27"))
    )
    (comp (ref "S1")
      (value "Set")
      (footprint "eagle-import:B3F-31XX")
      (libsource (lib "eagle-import") (part "31-XX"))
    )
    (comp (ref "S2")
      (value "Count")
      (footprint "eagle-import:B3F-31XX")
      (libsource (lib "eagle-import") (part "31-XX"))
    )
    (comp (ref "S3")
      (value "Reset")
      (footprint "eagle-import:TACTILE_SWITCH_SMD_6.0X3.5MM")
      (libsource (lib "eagle-import") (part "MOMENTARY-SWITCH-SPST-SMD-6.0X3.5MM"))
    )
    (comp (ref "TCK")
      (value "TPB1,27")
      (footprint "eagle-import:B1,27")
      (libsource (lib "eagle-import") (part "TPB1,27"))
    )
    (comp (ref "TDI")
      (value "TPB1,27")
      (footprint "eagle-import:B1,27")
      (libsource (lib "eagle-import") (part "TPB1,27"))
    )
    (comp (ref "TDO")
      (value "TPB1,27")
      (footprint "eagle-import:B1,27")
      (libsource (lib "eagle-import") (part "TPB1,27"))
    )
    (comp (ref "TMS")
      (value "TPB1,27")
      (footprint "eagle-import:B1,27")
      (libsource (lib "eagle-import") (part "TPB1,27"))
    )
    (comp (ref "U$3")
      (value "LOGO_PASCAL_GESELLEMPTY")
      (footprint "eagle-import:EMPTY")
      (libsource (lib "eagle-import") (part "LOGO_PASCAL_GESELLEMPTY"))
    )
    (comp (ref "U5")
      (value "GD32VF103T")
      (footprint "eagle-import:QFN-36")
      (libsource (lib "eagle-import") (part "GD32VF103T"))
    )
    (comp (ref "U6")
      (value "RV-3032-C7")
      (footprint "eagle-import:RV-3028-C7")
      (libsource (lib "eagle-import") (part "RV-3032-C7"))
    )
    (comp (ref "Y1")
      (value "8MHz")
      (footprint "eagle-import:RESONATOR-SMD-3.2X1.3")
      (libsource (lib "eagle-import") (part "RESONATOR-8MHZSMD_3.2X1.3"))
    )
  )
  (nets
    (net (code "1") (name "+3V3") (class "Default")
      (node (ref "C23") (pin "1") (pinfunction "1_1") (pintype "passive"))
      (node (ref "C29") (pin "1") (pinfunction "1_1") (pintype "passive"))
      (node (ref "C3") (pin "1") (pinfunction "1_1") (pintype "passive"))
      (node (ref "C4") (pin "1") (pinfunction "1_1") (pintype "passive"))
      (node (ref "C5") (pin "1") (pinfunction "1_1") (pintype "passive"))
      (node (ref "C6") (pin "1") (pinfunction "1_1") (pintype "passive"))
      (node (ref "C7") (pin "1") (pinfunction "1_1") (pintype "passive"))
      (node (ref "C8") (pin "1") (pinfunction "1_1") (pintype "passive"))
      (node (ref "J3") (pin "1") (pinfunction "1_1") (pintype "bidirectional"))
      (node (ref "J6") (pin "2") (pinfunction "2_2") (pintype "passive"))
      (node (ref "J6") (pin "6") (pinfunction "6_6") (pintype "passive"))
      (node (ref "L3") (pin "1") (pinfunction "1_1") (pintype "passive"))
      (node (ref "R16") (pin "2") (pinfunction "2_2") (pintype "passive"))
      (node (ref "R18") (pin "2") (pinfunction "2_2") (pintype "passive"))
      (node (ref "R19") (pin "2") (pinfunction "2_2") (pintype "passive"))
      (node (ref "R27") (pin "2") (pinfunction "2_2") (pintype "passive"))
      (node (ref "R28") (pin "2") (pinfunction "2_2") (pintype "passive"))
      (node (ref "S1") (pin "2") (pinfunction "S_2") (pintype "passive"))
      (node (ref "S2") (pin "2") (pinfunction "S_2") (pintype "passive"))
      (node (ref "U2") (pin "4") (pinfunction "VFB_4") (pintype "power_in"))
      (node (ref "U5") (pin "1") (pinfunction "VCC_1") (pintype "power_in"))
      (node (ref "U5") (pin "19") (pinfunction "VCC_19") (pintype "power_in"))
      (node (ref "U5") (pin "27") (pinfunction "VCC_27") (pintype "power_in"))
      (node (ref "U5") (pin "6") (pinfunction "VCCA_6") (pintype "power_in"))
      (node (ref "U6") (pin "6") (pinfunction "VDD_6") (pintype "bidirectional"))
    )
    (net (code "2") (name "+5V") (class "Default")
      (node (ref "C2") (pin "1") (pinfunction "1_1") (pintype "passive"))
      (node (ref "C22") (pin "1") (pinfunction "1_1") (pintype "passive"))
      (node (ref "L2") (pin "1") (pinfunction "1_1") (pintype "passive"))
      (node (ref "U2") (pin "1") (pinfunction "VIN_1") (pintype "power_in"))
      (node (ref "U2") (pin "3") (pinfunction "~{SHDN}_3") (pintype "power_in"))
      (node (ref "U4") (pin "1") (pinfunction "VIN_1") (pintype "input"))
      (node (ref "U4") (pin "2") (pinfunction "VIN_2") (pintype "input"))
      (node (ref "U4") (pin "4") (pinfunction "VBIAS_4") (pintype "power_in"))
    )
    (net (code "3") (name "+170VDC") (class "Default")
      (node (ref "J4") (pin "1") (pinfunction "1_1") (pintype "bidirectional"))
      (node (ref "J4") (pin "2") (pinfunction "2_2") (pintype "bidirectional"))
      (node (ref "J7") (pin "1") (pinfunction "1_1") (pintype "passive"))
      (node (ref "N1") (pin "A") (pinfunction "A_A") (pintype "power_in"))
      (node (ref "N2") (pin "A") (pinfunction "A_A") (pintype "power_in"))
      (node (ref "N3") (pin "A") (pinfunction "A_A") (pintype "power_in"))
      (node (ref "N4") (pin "A") (pinfunction "A_A") (pintype "power_in"))
    )
    (net (code "4") (name "00") (class "Default")
      (node (ref "T3") (pin "1") (pinfunction "B_1") (pintype "passive"))
      (node (ref "U7") (pin "9") (pinfunction "PWM6_9") (pintype "output"))
    )
    (net (code "5") (name "01") (class "Default")
      (node (ref "T11") (pin "1") (pinfunction "B_1") (pintype "passive"))
      (node (ref "U7") (pin "10") (pinfunction "PWM7_10") (pintype "output"))
    )
    (net (code "6") (name "02") (class "Default")
      (node (ref "T10") (pin "1") (pinfunction "B_1") (pintype "passive"))
      (node (ref "U7") (pin "12") (pinfunction "PWM8_12") (pintype "output"))
    )
    (net (code "7") (name "03") (class "Default")
      (node (ref "T9") (pin "1") (pinfunction "B_1") (pintype "passive"))
      (node (ref "U7") (pin "13") (pinfunction "PWM9_13") (pintype "output"))
    )
    (net (code "8") (name "04") (class "Default")
      (node (ref "T8") (pin "1") (pinfunction "B_1") (pintype "passive"))
      (node (ref "U7") (pin "14") (pinfunction "PWM10_14") (pintype "output"))
    )
    (net (code "9") (name "05") (class "Default")
      (node (ref "T7") (pin "1") (pinfunction "B_1") (pintype "passive"))
      (node (ref "U7") (pin "15") (pinfunction "PWM11_15") (pintype "output"))
    )
    (net (code "10") (name "06") (class "Default")
      (node (ref "T6") (pin "1") (pinfunction "B_1") (pintype "passive"))
      (node (ref "U7") (pin "16") (pinfunction "PWM12_16") (pintype "output"))
    )
    (net (code "11") (name "07") (class "Default")
      (node (ref "T2") (pin "1") (pinfunction "B_1") (pintype "passive"))
      (node (ref "U7") (pin "17") (pinfunction "PWM13_17") (pintype "output"))
    )
    (net (code "12") (name "08") (class "Default")
      (node (ref "T5") (pin "1") (pinfunction "B_1") (pintype "passive"))
      (node (ref "U7") (pin "18") (pinfunction "PWM14_18") (pintype "output"))
    )
    (net (code "13") (name "09") (class "Default")
      (node (ref "T4") (pin "1") (pinfunction "B_1") (pintype "passive"))
      (node (ref "U7") (pin "19") (pinfunction "PWM15_19") (pintype "output"))
    )
    (net (code "14") (name "10") (class "Default")
      (node (ref "T13") (pin "1") (pinfunction "B_1") (pintype "passive"))
      (node (ref "U7") (pin "3") (pinfunction "PWM0_3") (pintype "output"))
    )
    (net (code "15") (name "11") (class "Default")
      (node (ref "T22") (pin "1") (pinfunction "B_1") (pintype "passive"))
      (node (ref "U7") (pin "4") (pinfunction "PWM1_4") (pintype "output"))
    )
    (net (code "16") (name "12") (class "Default")
      (node (ref "T21") (pin "1") (pinfunction "B_1") (pintype "passive"))
      (node (ref "U7") (pin "5") (pinfunction "PWM2_5") (pintype "output"))
    )
    (net (code "17") (name "13") (class "Default")
      (node (ref "T20") (pin "1") (pinfunction "B_1") (pintype "passive"))
      (node (ref "U7") (pin "6") (pinfunction "PWM3_6") (pintype "output"))
    )
    (net (code "18") (name "14") (class "Default")
      (node (ref "T19") (pin "1") (pinfunction "B_1") (pintype "passive"))
      (node (ref "U7") (pin "7") (pinfunction "PWM4_7") (pintype "output"))
    )
    (net (code "19") (name "15") (class "Default")
      (node (ref "T18") (pin "1") (pinfunction "B_1") (pintype "passive"))
      (node (ref "U8") (pin "14") (pinfunction "PWM10_14") (pintype "output"))
    )
    (net (code "20") (name "16") (class "Default")
      (node (ref "T17") (pin "1") (pinfunction "B_1") (pintype "passive"))
      (node (ref "U8") (pin "15") (pinfunction "PWM11_15") (pintype "output"))
    )
    (net (code "21") (name "17") (class "Default")
      (node (ref "T16") (pin "1") (pinfunction "B_1") (pintype "passive"))
      (node (ref "U8") (pin "16") (pinfunction "PWM12_16") (pintype "output"))
    )
    (net (code "22") (name "18") (class "Default")
      (node (ref "T15") (pin "1") (pinfunction "B_1") (pintype "passive"))
      (node (ref "U8") (pin "17") (pinfunction "PWM13_17") (pintype "output"))
    )
    (net (code "23") (name "19") (class "Default")
      (node (ref "T14") (pin "1") (pinfunction "B_1") (pintype "passive"))
      (node (ref "U8") (pin "18") (pinfunction "PWM14_18") (pintype "output"))
    )
    (net (code "24") (name "20") (class "Default")
      (node (ref "T23") (pin "1") (pinfunction "B_1") (pintype "passive"))
      (node (ref "U8") (pin "3") (pinfunction "PWM0_3") (pintype "output"))
    )
    (net (code "25") (name "21") (class "Default")
      (node (ref "T32") (pin "1") (pinfunction "B_1") (pintype "passive"))
      (node (ref "U8") (pin "4") (pinfunction "PWM1_4") (pintype "output"))
    )
    (net (code "26") (name "22") (class "Default")
      (node (ref "T31") (pin "1") (pinfunction "B_1") (pintype "passive"))
      (node (ref "U8") (pin "5") (pinfunction "PWM2_5") (pintype "output"))
    )
    (net (code "27") (name "23") (class "Default")
      (node (ref "T30") (pin "1") (pinfunction "B_1") (pintype "passive"))
      (node (ref "U8") (pin "6") (pinfunction "PWM3_6") (pintype "output"))
    )
    (net (code "28") (name "24") (class "Default")
      (node (ref "T29") (pin "1") (pinfunction "B_1") (pintype "passive"))
      (node (ref "U8") (pin "7") (pinfunction "PWM4_7") (pintype "output"))
    )
    (net (code "29") (name "25") (class "Default")
      (node (ref "T28") (pin "1") (pinfunction "B_1") (pintype "passive"))
      (node (ref "U8") (pin "8") (pinfunction "PWM5_8") (pintype "output"))
    )
    (net (code "30") (name "26") (class "Default")
      (node (ref "T27") (pin "1") (pinfunction "B_1") (pintype "passive"))
      (node (ref "U8") (pin "9") (pinfunction "PWM6_9") (pintype "output"))
    )
    (net (code "31") (name "27") (class "Default")
      (node (ref "T26") (pin "1") (pinfunction "B_1") (pintype "passive"))
      (node (ref "U8") (pin "10") (pinfunction "PWM7_10") (pintype "output"))
    )
    (net (code "32") (name "28") (class "Default")
      (node (ref "T25") (pin "1") (pinfunction "B_1") (pintype "passive"))
      (node (ref "U8") (pin "12") (pinfunction "PWM8_12") (pintype "output"))
    )
    (net (code "33") (name "29") (class "Default")
      (node (ref "T24") (pin "1") (pinfunction "B_1") (pintype "passive"))
      (node (ref "U8") (pin "13") (pinfunction "PWM9_13") (pintype "output"))
    )
    (net (code "34") (name "30") (class "Default")
      (node (ref "T1") (pin "1") (pinfunction "B_1") (pintype "passive"))
      (node (ref "U9") (pin "3") (pinfunction "PWM0_3") (pintype "output"))
    )
    (net (code "35") (name "31") (class "Default")
      (node (ref "T40") (pin "1") (pinfunction "B_1") (pintype "passive"))
      (node (ref "U9") (pin "4") (pinfunction "PWM1_4") (pintype "output"))
    )
    (net (code "36") (name "32") (class "Default")
      (node (ref "T39") (pin "1") (pinfunction "B_1") (pintype "passive"))
      (node (ref "U9") (pin "5") (pinfunction "PWM2_5") (pintype "output"))
    )
    (net (code "37") (name "33") (class "Default")
      (node (ref "T38") (pin "1") (pinfunction "B_1") (pintype "passive"))
      (node (ref "U9") (pin "6") (pinfunction "PWM3_6") (pintype "output"))
    )
    (net (code "38") (name "34") (class "Default")
      (node (ref "T37") (pin "1") (pinfunction "B_1") (pintype "passive"))
      (node (ref "U9") (pin "7") (pinfunction "PWM4_7") (pintype "output"))
    )
    (net (code "39") (name "35") (class "Default")
      (node (ref "T36") (pin "1") (pinfunction "B_1") (pintype "passive"))
      (node (ref "U9") (pin "8") (pinfunction "PWM5_8") (pintype "output"))
    )
    (net (code "40") (name "36") (class "Default")
      (node (ref "T35") (pin "1") (pinfunction "B_1") (pintype "passive"))
      (node (ref "U9") (pin "9") (pinfunction "PWM6_9") (pintype "output"))
    )
    (net (code "41") (name "37") (class "Default")
      (node (ref "T34") (pin "1") (pinfunction "B_1") (pintype "passive"))
      (node (ref "U9") (pin "10") (pinfunction "PWM7_10") (pintype "output"))
    )
    (net (code "42") (name "38") (class "Default")
      (node (ref "T33") (pin "1") (pinfunction "B_1") (pintype "passive"))
      (node (ref "U9") (pin "12") (pinfunction "PWM8_12") (pintype "output"))
    )
    (net (code "43") (name "39") (class "Default")
      (node (ref "T12") (pin "1") (pinfunction "B_1") (pintype "passive"))
      (node (ref "U9") (pin "13") (pinfunction "PWM9_13") (pintype "output"))
    )
    (net (code "44") (name "AGND") (class "Default")
      (node (ref "C30") (pin "2") (pinfunction "2_2") (pintype "passive"))
      (node (ref "C31") (pin "2") (pinfunction "2_2") (pintype "passive"))
      (node (ref "C32") (pin "2") (pinfunction "2_2") (pintype "passive"))
      (node (ref "J4") (pin "5") (pinfunction "5_5") (pintype "bidirectional"))
      (node (ref "J4") (pin "6") (pinfunction "6_6") (pintype "bidirectional"))
      (node (ref "J5") (pin "5") (pinfunction "5_5") (pintype "bidirectional"))
      (node (ref "J5") (pin "6") (pinfunction "6_6") (pintype "bidirectional"))
      (node (ref "R29") (pin "1") (pinfunction "1_1") (pintype "passive"))
      (node (ref "R30") (pin "1") (pinfunction "1_1") (pintype "passive"))
      (node (ref "R31") (pin "1") (pinfunction "1_1") (pintype "passive"))
      (node (ref "R32") (pin "1") (pinfunction "1_1") (pintype "passive"))
      (node (ref "R33") (pin "1") (pinfunction "1_1") (pintype "passive"))
      (node (ref "R34") (pin "1") (pinfunction "1_1") (pintype "passive"))
      (node (ref "R35") (pin "1") (pinfunction "1_1") (pintype "passive"))
      (node (ref "R36") (pin "1") (pinfunction "1_1") (pintype "passive"))
      (node (ref "R37") (pin "1") (pinfunction "1_1") (pintype "passive"))
      (node (ref "R38") (pin "1") (pinfunction "1_1") (pintype "passive"))
      (node (ref "R39") (pin "1") (pinfunction "1_1") (pintype "passive"))
      (node (ref "R40") (pin "1") (pinfunction "1_1") (pintype "passive"))
      (node (ref "R41") (pin "1") (pinfunction "1_1") (pintype "passive"))
      (node (ref "R42") (pin "1") (pinfunction "1_1") (pintype "passive"))
      (node (ref "R43") (pin "1") (pinfunction "1_1") (pintype "passive"))
      (node (ref "R44") (pin "1") (pinfunction "1_1") (pintype "passive"))
      (node (ref "R45") (pin "1") (pinfunction "1_1") (pintype "passive"))
      (node (ref "R46") (pin "1") (pinfunction "1_1") (pintype "passive"))
      (node (ref "R47") (pin "1") (pinfunction "1_1") (pintype "passive"))
      (node (ref "R48") (pin "1") (pinfunction "1_1") (pintype "passive"))
      (node (ref "R49") (pin "1") (pinfunction "1_1") (pintype "passive"))
      (node (ref "R50") (pin "1") (pinfunction "1_1") (pintype "passive"))
      (node (ref "R51") (pin "1") (pinfunction "1_1") (pintype "passive"))
      (node (ref "R52") (pin "1") (pinfunction "1_1") (pintype "passive"))
      (node (ref "R53") (pin "1") (pinfunction "1_1") (pintype "passive"))
      (node (ref "R54") (pin "1") (pinfunction "1_1") (pintype "passive"))
      (node (ref "R55") (pin "1") (pinfunction "1_1") (pintype "passive"))
      (node (ref "R56") (pin "1") (pinfunction "1_1") (pintype "passive"))
      (node (ref "R57") (pin "1") (pinfunction "1_1") (pintype "passive"))
      (node (ref "R58") (pin "1") (pinfunction "1_1") (pintype "passive"))
      (node (ref "R59") (pin "1") (pinfunction "1_1") (pintype "passive"))
      (node (ref "R60") (pin "1") (pinfunction "1_1") (pintype "passive"))
      (node (ref "R61") (pin "1") (pinfunction "1_1") (pintype "passive"))
      (node (ref "R62") (pin "1") (pinfunction "1_1") (pintype "passive"))
      (node (ref "R63") (pin "1") (pinfunction "1_1") (pintype "passive"))
      (node (ref "R64") (pin "1") (pinfunction "1_1") (pintype "passive"))
      (node (ref "R65") (pin "1") (pinfunction "1_1") (pintype "passive"))
      (node (ref "R66") (pin "1") (pinfunction "1_1") (pintype "passive"))
      (node (ref "R67") (pin "1") (pinfunction "1_1") (pintype "passive"))
      (node (ref "R68") (pin "1") (pinfunction "1_1") (pintype "passive"))
      (node (ref "R69") (pin "1") (pinfunction "1_1") (pintype "passive"))
      (node (ref "U7") (pin "1") (pinfunction "A3_1") (pintype "input"))
      (node (ref "U7") (pin "11") (pinfunction "GND_11") (pintype "power_in"))
      (node (ref "U7") (pin "2") (pinfunction "A4_2") (pintype "input"))
      (node (ref "U7") (pin "21") (pinfunction "A5_21") (pintype "input"))
      (node (ref "U7") (pin "22") (pinfunction "EXTCLK_22") (pintype "input"))
      (node (ref "U7") (pin "26") (pinfunction "A0_26") (pintype "input"))
      (node (ref "U7") (pin "27") (pinfunction "A1_27") (pintype "input"))
      (node (ref "U7") (pin "28") (pinfunction "A2_28") (pintype "input"))
      (node (ref "U7") (pin "TH") (pinfunction "GND_TH") (pintype "power_in"))
      (node (ref "U8") (pin "1") (pinfunction "A3_1") (pintype "input"))
      (node (ref "U8") (pin "11") (pinfunction "GND_11") (pintype "power_in"))
      (node (ref "U8") (pin "2") (pinfunction "A4_2") (pintype "input"))
      (node (ref "U8") (pin "21") (pinfunction "A5_21") (pintype "input"))
      (node (ref "U8") (pin "22") (pinfunction "EXTCLK_22") (pintype "input"))
      (node (ref "U8") (pin "27") (pinfunction "A1_27") (pintype "input"))
      (node (ref "U8") (pin "28") (pinfunction "A2_28") (pintype "input"))
      (node (ref "U8") (pin "TH") (pinfunction "GND_TH") (pintype "power_in"))
      (node (ref "U9") (pin "1") (pinfunction "A3_1") (pintype "input"))
      (node (ref "U9") (pin "11") (pinfunction "GND_11") (pintype "power_in"))
      (node (ref "U9") (pin "2") (pinfunction "A4_2") (pintype "input"))
      (node (ref "U9") (pin "21") (pinfunction "A5_21") (pintype "input"))
      (node (ref "U9") (pin "22") (pinfunction "EXTCLK_22") (pintype "input"))
      (node (ref "U9") (pin "26") (pinfunction "A0_26") (pintype "input"))
      (node (ref "U9") (pin "28") (pinfunction "A2_28") (pintype "input"))
      (node (ref "U9") (pin "TH") (pinfunction "GND_TH") (pintype "power_in"))
    )
    (net (code "45") (name "BOOST_~{SHDN}") (class "Default")
      (node (ref "R15") (pin "1") (pinfunction "1_1") (pintype "passive"))
      (node (ref "U3") (pin "9") (pinfunction "~{SHDN}/UVLO_9") (pintype "input"))
      (node (ref "U5") (pin "16") (pinfunction "PB1_16") (pintype "bidirectional"))
    )
    (net (code "46") (name "BTN_CNT") (class "Default")
      (node (ref "C26") (pin "1") (pinfunction "1_1") (pintype "passive"))
      (node (ref "R20") (pin "2") (pinfunction "2_2") (pintype "passive"))
      (node (ref "R23") (pin "1") (pinfunction "1_1") (pintype "passive"))
      (node (ref "U5") (pin "8") (pinfunction "PA1_8") (pintype "bidirectional"))
    )
    (net (code "47") (name "BTN_SET") (class "Default")
      (node (ref "C25") (pin "1") (pinfunction "1_1") (pintype "passive"))
      (node (ref "R21") (pin "1") (pinfunction "1_1") (pintype "passive"))
      (node (ref "R22") (pin "2") (pinfunction "2_2") (pintype "passive"))
      (node (ref "U5") (pin "7") (pinfunction "PA0_7") (pintype "bidirectional"))
    )
    (net (code "48") (name "CC1") (class "Default")
      (node (ref "D2") (pin "C") (pinfunction "C_C") (pintype "passive"))
      (node (ref "R4") (pin "2") (pinfunction "2_2") (pintype "passive"))
      (node (ref "U5") (pin "13") (pinfunction "PA6_13") (pintype "bidirectional"))
    )
    (net (code "49") (name "CC2") (class "Default")
      (node (ref "D1") (pin "C") (pinfunction "C_C") (pintype "passive"))
      (node (ref "R5") (pin "2") (pinfunction "2_2") (pintype "passive"))
      (node (ref "U5") (pin "14") (pinfunction "PA7_14") (pintype "bidirectional"))
    )
    (net (code "50") (name "CRG_ON") (class "Default")
      (node (ref "U4") (pin "3") (pinfunction "ON_3") (pintype "input"))
      (node (ref "U5") (pin "15") (pinfunction "PB0_15") (pintype "bidirectional"))
    )
    (net (code "51") (name "D+") (class "Default")
      (node (ref "J1") (pin "A6") (pinfunction "DP1_A6") (pintype "bidirectional"))
      (node (ref "J1") (pin "B6") (pinfunction "DP2_B6") (pintype "bidirectional"))
      (node (ref "R26") (pin "2") (pinfunction "2_2") (pintype "passive"))
      (node (ref "U1") (pin "3") (pinfunction "3_3") (pintype "bidirectional"))
    )
    (net (code "52") (name "D-") (class "Default")
      (node (ref "J1") (pin "A7") (pinfunction "DN1_A7") (pintype "bidirectional"))
      (node (ref "J1") (pin "B7") (pinfunction "DN2_B7") (pintype "bidirectional"))
      (node (ref "R25") (pin "2") (pinfunction "2_2") (pintype "passive"))
      (node (ref "U1") (pin "2") (pinfunction "2_2") (pintype "bidirectional"))
    )
    (net (code "53") (name "GND") (class "Default")
      (node (ref "BT1") (pin "-") (pinfunction "-_-") (pintype "passive"))
      (node (ref "C1") (pin "2") (pinfunction "2_2") (pintype "passive"))
      (node (ref "C10") (pin "2") (pinfunction "2_2") (pintype "passive"))
      (node (ref "C12") (pin "2") (pinfunction "2_2") (pintype "passive"))
      (node (ref "C13") (pin "2") (pinfunction "2_2") (pintype "passive"))
      (node (ref "C14") (pin "2") (pinfunction "2_2") (pintype "passive"))
      (node (ref "C15") (pin "2") (pinfunction "2_2") (pintype "passive"))
      (node (ref "C16") (pin "2") (pinfunction "2_2") (pintype "passive"))
      (node (ref "C17") (pin "2") (pinfunction "2_2") (pintype "passive"))
      (node (ref "C18") (pin "2") (pinfunction "2_2") (pintype "passive"))
      (node (ref "C19") (pin "2") (pinfunction "2_2") (pintype "passive"))
      (node (ref "C2") (pin "2") (pinfunction "2_2") (pintype "passive"))
      (node (ref "C20") (pin "2") (pinfunction "2_2") (pintype "passive"))
      (node (ref "C21") (pin "2") (pinfunction "2_2") (pintype "passive"))
      (node (ref "C22") (pin "2") (pinfunction "2_2") (pintype "passive"))
      (node (ref "C23") (pin "2") (pinfunction "2_2") (pintype "passive"))
      (node (ref "C24") (pin "2") (pinfunction "2_2") (pintype "passive"))
      (node (ref "C25") (pin "2") (pinfunction "2_2") (pintype "passive"))
      (node (ref "C26") (pin "2") (pinfunction "2_2") (pintype "passive"))
      (node (ref "C29") (pin "2") (pinfunction "2_2") (pintype "passive"))
      (node (ref "C3") (pin "2") (pinfunction "2_2") (pintype "passive"))
      (node (ref "C4") (pin "2") (pinfunction "2_2") (pintype "passive"))
      (node (ref "C5") (pin "2") (pinfunction "2_2") (pintype "passive"))
      (node (ref "C6") (pin "2") (pinfunction "2_2") (pintype "passive"))
      (node (ref "C7") (pin "2") (pinfunction "2_2") (pintype "passive"))
      (node (ref "C8") (pin "2") (pinfunction "2_2") (pintype "passive"))
      (node (ref "C9") (pin "2") (pinfunction "2_2") (pintype "passive"))
      (node (ref "D1") (pin "A") (pinfunction "A_A") (pintype "passive"))
      (node (ref "D2") (pin "A") (pinfunction "A_A") (pintype "passive"))
      (node (ref "GND") (pin "TP") (pinfunction "TP_TP") (pintype "input"))
      (node (ref "J1") (pin "A1") (pinfunction "GND_A1") (pintype "power_in"))
      (node (ref "J1") (pin "B1") (pinfunction "GND_B1") (pintype "power_in"))
      (node (ref "J2") (pin "5") (pinfunction "5_5") (pintype "bidirectional"))
      (node (ref "J2") (pin "6") (pinfunction "6_6") (pintype "bidirectional"))
      (node (ref "J3") (pin "5") (pinfunction "5_5") (pintype "bidirectional"))
      (node (ref "J3") (pin "6") (pinfunction "6_6") (pintype "bidirectional"))
      (node (ref "J6") (pin "7") (pinfunction "7_7") (pintype "passive"))
      (node (ref "L4") (pin "1") (pinfunction "S1_1") (pintype "passive"))
      (node (ref "R1") (pin "1") (pinfunction "1_1") (pintype "passive"))
      (node (ref "R11") (pin "1") (pinfunction "1_1") (pintype "passive"))
      (node (ref "R12") (pin "1") (pinfunction "1_1") (pintype "passive"))
      (node (ref "R14") (pin "1") (pinfunction "1_1") (pintype "passive"))
      (node (ref "R2") (pin "1") (pinfunction "1_1") (pintype "passive"))
      (node (ref "R20") (pin "1") (pinfunction "1_1") (pintype "passive"))
      (node (ref "R22") (pin "1") (pinfunction "1_1") (pintype "passive"))
      (node (ref "R24") (pin "1") (pinfunction "1_1") (pintype "passive"))
      (node (ref "R3") (pin "1") (pinfunction "1_1") (pintype "passive"))
      (node (ref "R9") (pin "1") (pinfunction "1_1") (pintype "passive"))
      (node (ref "S3") (pin "1") (pinfunction "1_1") (pintype "passive"))
      (node (ref "U1") (pin "1") (pinfunction "1_1") (pintype "bidirectional"))
      (node (ref "U2") (pin "2") (pinfunction "GND_2") (pintype "power_in"))
      (node (ref "U3") (pin "5") (pinfunction "SYNC_5") (pintype "input"))
      (node (ref "U3") (pin "EP") (pinfunction "GND_EP") (pintype "power_in"))
      (node (ref "U4") (pin "5") (pinfunction "GND_5") (pintype "power_in"))
      (node (ref "U4") (pin "TP") (pinfunction "GND_TP") (pintype "power_in"))
      (node (ref "U5") (pin "17") (pinfunction "PB2_17") (pintype "bidirectional"))
      (node (ref "U5") (pin "18") (pinfunction "GND_18") (pintype "power_in"))
      (node (ref "U5") (pin "26") (pinfunction "GND_26") (pintype "power_in"))
      (node (ref "U5") (pin "36") (pinfunction "GND_36") (pintype "power_in"))
      (node (ref "U5") (pin "5") (pinfunction "GNDA_5") (pintype "power_in"))
      (node (ref "U5") (pin "EP") (pinfunction "GND_EP") (pintype "power_in"))
      (node (ref "U6") (pin "5") (pinfunction "VSS_5") (pintype "bidirectional"))
      (node (ref "Y1") (pin "2") (pinfunction "2_2") (pintype "passive"))
    )
    (net (code "54") (name "HV_170VDC") (class "Default")
      (node (ref "C12") (pin "1") (pinfunction "1_1") (pintype "passive"))
      (node (ref "D3") (pin "C") (pinfunction "C_C") (pintype "passive"))
      (node (ref "J2") (pin "1") (pinfunction "1_1") (pintype "bidirectional"))
      (node (ref "J2") (pin "2") (pinfunction "2_2") (pintype "bidirectional"))
      (node (ref "R10") (pin "2") (pinfunction "2_2") (pintype "passive"))
    )
    (net (code "55") (name "H_B") (class "Default")
      (node (ref "R78") (pin "2") (pinfunction "2_2") (pintype "passive"))
      (node (ref "R81") (pin "2") (pinfunction "2_2") (pintype "passive"))
      (node (ref "U9") (pin "19") (pinfunction "PWM15_19") (pintype "output"))
    )
    (net (code "56") (name "H_G") (class "Default")
      (node (ref "R77") (pin "2") (pinfunction "2_2") (pintype "passive"))
      (node (ref "R80") (pin "2") (pinfunction "2_2") (pintype "passive"))
      (node (ref "U9") (pin "17") (pinfunction "PWM13_17") (pintype "output"))
    )
    (net (code "57") (name "H_R") (class "Default")
      (node (ref "R76") (pin "2") (pinfunction "2_2") (pintype "passive"))
      (node (ref "R79") (pin "2") (pinfunction "2_2") (pintype "passive"))
      (node (ref "U9") (pin "18") (pinfunction "PWM14_18") (pintype "output"))
    )
    (net (code "58") (name "JTCK") (class "Default")
      (node (ref "TCK") (pin "TP") (pinfunction "TP_TP") (pintype "input"))
      (node (ref "U5") (pin "28") (pinfunction "PA14_28") (pintype "bidirectional"))
    )
    (net (code "59") (name "JTDI") (class "Default")
      (node (ref "TDI") (pin "TP") (pinfunction "TP_TP") (pintype "input"))
      (node (ref "U5") (pin "29") (pinfunction "PA15_29") (pintype "bidirectional"))
    )
    (net (code "60") (name "JTDO") (class "Default")
      (node (ref "TDO") (pin "TP") (pinfunction "TP_TP") (pintype "input"))
      (node (ref "U5") (pin "30") (pinfunction "PB3_30") (pintype "bidirectional"))
    )
    (net (code "61") (name "JTMS") (class "Default")
      (node (ref "TMS") (pin "TP") (pinfunction "TP_TP") (pintype "input"))
      (node (ref "U5") (pin "25") (pinfunction "PA13_25") (pintype "bidirectional"))
    )
    (net (code "62") (name "MCU_RX") (class "Default")
      (node (ref "J6") (pin "8") (pinfunction "8_8") (pintype "passive"))
      (node (ref "U5") (pin "10") (pinfunction "PA3_10") (pintype "bidirectional"))
    )
    (net (code "63") (name "MCU_TX") (class "Default")
      (node (ref "J6") (pin "1") (pinfunction "1_1") (pintype "passive"))
      (node (ref "U5") (pin "9") (pinfunction "PA2_9") (pintype "bidirectional"))
    )
    (net (code "64") (name "M_B") (class "Default")
      (node (ref "R70") (pin "2") (pinfunction "2_2") (pintype "passive"))
      (node (ref "R75") (pin "2") (pinfunction "2_2") (pintype "passive"))
      (node (ref "U9") (pin "16") (pinfunction "PWM12_16") (pintype "output"))
    )
    (net (code "65") (name "M_G") (class "Default")
      (node (ref "R71") (pin "2") (pinfunction "2_2") (pintype "passive"))
      (node (ref "R74") (pin "2") (pinfunction "2_2") (pintype "passive"))
      (node (ref "U9") (pin "14") (pinfunction "PWM10_14") (pintype "output"))
    )
    (net (code "66") (name "M_R") (class "Default")
      (node (ref "R72") (pin "2") (pinfunction "2_2") (pintype "passive"))
      (node (ref "R73") (pin "2") (pinfunction "2_2") (pintype "passive"))
      (node (ref "U9") (pin "15") (pinfunction "PWM11_15") (pintype "output"))
    )
    (net (code "67") (name "NJTRST") (class "Default")
      (node (ref "RST") (pin "TP") (pinfunction "TP_TP") (pintype "input"))
      (node (ref "U5") (pin "31") (pinfunction "PB4_31") (pintype "bidirectional"))
    )
    (net (code "68") (name "Net-(C1-Pad1)") (class "Default")
      (node (ref "C1") (pin "1") (pinfunction "1_1") (pintype "passive"))
      (node (ref "J1") (pin "SHB1") (pinfunction "SHLD_SHB1") (pintype "passive"))
      (node (ref "J1") (pin "SHB2") (pinfunction "SHLD_SHB2") (pintype "passive"))
      (node (ref "J1") (pin "SHB3") (pinfunction "SHLD_SHB3") (pintype "passive"))
      (node (ref "J1") (pin "SHB4") (pinfunction "SHLD_SHB4") (pintype "passive"))
      (node (ref "J1") (pin "SHT1") (pinfunction "SHLD_SHT1") (pintype "passive"))
      (node (ref "J1") (pin "SHT2") (pinfunction "SHLD_SHT2") (pintype "passive"))
      (node (ref "J1") (pin "SHT3") (pinfunction "SHLD_SHT3") (pintype "passive"))
      (node (ref "J1") (pin "SHT4") (pinfunction "SHLD_SHT4") (pintype "passive"))
      (node (ref "R3") (pin "2") (pinfunction "2_2") (pintype "passive"))
    )
    (net (code "69") (name "Net-(C9-Pad1)") (class "Default")
      (node (ref "C9") (pin "1") (pinfunction "1_1") (pintype "passive"))
      (node (ref "R8") (pin "1") (pinfunction "1_1") (pintype "passive"))
    )
    (net (code "70") (name "Net-(C11-Pad2)") (class "Default")
      (node (ref "C11") (pin "2") (pinfunction "2_2") (pintype "passive"))
      (node (ref "D4") (pin "C") (pinfunction "C_C") (pintype "passive"))
      (node (ref "R6") (pin "1") (pinfunction "1_1") (pintype "passive"))
    )
    (net (code "71") (name "Net-(D4-PadA)") (class "Default")
      (node (ref "D4") (pin "A") (pinfunction "A_A") (pintype "passive"))
      (node (ref "L4") (pin "3") (pinfunction "P2_3") (pintype "passive"))
      (node (ref "L4") (pin "4") (pinfunction "P2_4") (pintype "passive"))
      (node (ref "Q1") (pin "5") (pinfunction "D_5") (pintype "passive"))
      (node (ref "Q1") (pin "6") (pinfunction "D_6") (pintype "passive"))
      (node (ref "Q1") (pin "7") (pinfunction "D_7") (pintype "passive"))
      (node (ref "Q1") (pin "8") (pinfunction "D_8") (pintype "passive"))
      (node (ref "Q1") (pin "THERMAL") (pinfunction "D_THERMAL") (pintype "passive"))
    )
    (net (code "72") (name "Net-(D5-B-)") (class "Default")
      (node (ref "D5") (pin "2") (pinfunction "B-_2") (pintype "passive"))
      (node (ref "R70") (pin "1") (pinfunction "1_1") (pintype "passive"))
    )
    (net (code "73") (name "Net-(D5-G-)") (class "Default")
      (node (ref "D5") (pin "4") (pinfunction "G-_4") (pintype "passive"))
      (node (ref "R72") (pin "1") (pinfunction "1_1") (pintype "passive"))
    )
    (net (code "74") (name "Net-(D5-R-)") (class "Default")
      (node (ref "D5") (pin "3") (pinfunction "R-_3") (pintype "passive"))
      (node (ref "R71") (pin "1") (pinfunction "1_1") (pintype "passive"))
    )
    (net (code "75") (name "Net-(D6-B-)") (class "Default")
      (node (ref "D6") (pin "2") (pinfunction "B-_2") (pintype "passive"))
      (node (ref "R75") (pin "1") (pinfunction "1_1") (pintype "passive"))
    )
    (net (code "76") (name "Net-(D6-G-)") (class "Default")
      (node (ref "D6") (pin "4") (pinfunction "G-_4") (pintype "passive"))
      (node (ref "R73") (pin "1") (pinfunction "1_1") (pintype "passive"))
    )
    (net (code "77") (name "Net-(D6-R-)") (class "Default")
      (node (ref "D6") (pin "3") (pinfunction "R-_3") (pintype "passive"))
      (node (ref "R74") (pin "1") (pinfunction "1_1") (pintype "passive"))
    )
    (net (code "78") (name "Net-(D7-B-)") (class "Default")
      (node (ref "D7") (pin "2") (pinfunction "B-_2") (pintype "passive"))
      (node (ref "R78") (pin "1") (pinfunction "1_1") (pintype "passive"))
    )
    (net (code "79") (name "Net-(D7-G-)") (class "Default")
      (node (ref "D7") (pin "4") (pinfunction "G-_4") (pintype "passive"))
      (node (ref "R76") (pin "1") (pinfunction "1_1") (pintype "passive"))
    )
    (net (code "80") (name "Net-(D7-R-)") (class "Default")
      (node (ref "D7") (pin "3") (pinfunction "R-_3") (pintype "passive"))
      (node (ref "R77") (pin "1") (pinfunction "1_1") (pintype "passive"))
    )
    (net (code "81") (name "Net-(D8-B-)") (class "Default")
      (node (ref "D8") (pin "2") (pinfunction "B-_2") (pintype "passive"))
      (node (ref "R81") (pin "1") (pinfunction "1_1") (pintype "passive"))
    )
    (net (code "82") (name "Net-(D8-G-)") (class "Default")
      (node (ref "D8") (pin "4") (pinfunction "G-_4") (pintype "passive"))
      (node (ref "R79") (pin "1") (pinfunction "1_1") (pintype "passive"))
    )
    (net (code "83") (name "Net-(D8-R-)") (class "Default")
      (node (ref "D8") (pin "3") (pinfunction "R-_3") (pintype "passive"))
      (node (ref "R80") (pin "1") (pinfunction "1_1") (pintype "passive"))
    )
    (net (code "84") (name "Net-(J1-CC1)") (class "Default")
      (node (ref "J1") (pin "A5") (pinfunction "CC1_A5") (pintype "output"))
      (node (ref "R2") (pin "2") (pinfunction "2_2") (pintype "passive"))
      (node (ref "R4") (pin "1") (pinfunction "1_1") (pintype "passive"))
    )
    (net (code "85") (name "Net-(J1-CC2)") (class "Default")
      (node (ref "J1") (pin "B5") (pinfunction "CC2_B5") (pintype "output"))
      (node (ref "R1") (pin "2") (pinfunction "2_2") (pintype "passive"))
      (node (ref "R5") (pin "1") (pinfunction "1_1") (pintype "passive"))
    )
    (net (code "86") (name "Net-(J1-VBUS-PadA4)") (class "Default")
      (node (ref "J1") (pin "A4") (pinfunction "VBUS_A4") (pintype "power_in"))
      (node (ref "J1") (pin "B4") (pinfunction "VBUS_B4") (pintype "power_in"))
      (node (ref "L1") (pin "2") (pinfunction "2_2") (pintype "passive"))
      (node (ref "U1") (pin "4") (pinfunction "4_4") (pintype "bidirectional"))
    )
    (net (code "87") (name "Net-(L1-Pad1)") (class "Default")
      (node (ref "L1") (pin "1") (pinfunction "1_1") (pintype "passive"))
      (node (ref "L2") (pin "2") (pinfunction "2_2") (pintype "passive"))
    )
    (net (code "88") (name "Net-(L4-S2)") (class "Default")
      (node (ref "D3") (pin "A") (pinfunction "A_A") (pintype "passive"))
      (node (ref "L4") (pin "8") (pinfunction "S2_8") (pintype "passive"))
    )
    (net (code "89") (name "Net-(Q1-G)") (class "Default")
      (node (ref "Q1") (pin "4") (pinfunction "G_4") (pintype "passive"))
      (node (ref "R7") (pin "2") (pinfunction "2_2") (pintype "passive"))
    )
    (net (code "90") (name "Net-(Q1-S-Pad1)") (class "Default")
      (node (ref "Q1") (pin "1") (pinfunction "S_1") (pintype "passive"))
      (node (ref "Q1") (pin "2") (pinfunction "S_2") (pintype "passive"))
      (node (ref "Q1") (pin "3") (pinfunction "S_3") (pintype "passive"))
      (node (ref "R12") (pin "2") (pinfunction "2_2") (pintype "passive"))
      (node (ref "R13") (pin "2") (pinfunction "2_2") (pintype "passive"))
    )
    (net (code "91") (name "Net-(R17-Pad1)") (class "Default")
      (node (ref "R17") (pin "1") (pinfunction "1_1") (pintype "passive"))
      (node (ref "S3") (pin "2") (pinfunction "2_2") (pintype "passive"))
    )
    (net (code "92") (name "Net-(S1-P)") (class "Default")
      (node (ref "R21") (pin "2") (pinfunction "2_2") (pintype "passive"))
      (node (ref "R24") (pin "2") (pinfunction "2_2") (pintype "passive"))
      (node (ref "S1") (pin "1") (pinfunction "P_1") (pintype "passive"))
      (node (ref "U5") (pin "35") (pinfunction "BOOT0_35") (pintype "input"))
    )
    (net (code "93") (name "Net-(S2-P)") (class "Default")
      (node (ref "R23") (pin "2") (pinfunction "2_2") (pintype "passive"))
      (node (ref "S2") (pin "1") (pinfunction "P_1") (pintype "passive"))
    )
    (net (code "94") (name "Net-(T1-C)") (class "Default")
      (node (ref "N4") (pin "0") (pinfunction "0_0") (pintype "output"))
      (node (ref "T1") (pin "3") (pinfunction "C_3") (pintype "passive"))
    )
    (net (code "95") (name "Net-(T1-E)") (class "Default")
      (node (ref "R59") (pin "2") (pinfunction "2_2") (pintype "passive"))
      (node (ref "T1") (pin "2") (pinfunction "E_2") (pintype "passive"))
    )
    (net (code "96") (name "Net-(T2-C)") (class "Default")
      (node (ref "N1") (pin "7") (pinfunction "7_7") (pintype "output"))
      (node (ref "T2") (pin "3") (pinfunction "C_3") (pintype "passive"))
    )
    (net (code "97") (name "Net-(T2-E)") (class "Default")
      (node (ref "R32") (pin "2") (pinfunction "2_2") (pintype "passive"))
      (node (ref "T2") (pin "2") (pinfunction "E_2") (pintype "passive"))
    )
    (net (code "98") (name "Net-(T3-C)") (class "Default")
      (node (ref "N1") (pin "0") (pinfunction "0_0") (pintype "output"))
      (node (ref "T3") (pin "3") (pinfunction "C_3") (pintype "passive"))
    )
    (net (code "99") (name "Net-(T3-E)") (class "Default")
      (node (ref "R29") (pin "2") (pinfunction "2_2") (pintype "passive"))
      (node (ref "T3") (pin "2") (pinfunction "E_2") (pintype "passive"))
    )
    (net (code "100") (name "Net-(T4-C)") (class "Default")
      (node (ref "N1") (pin "9") (pinfunction "9_9") (pintype "output"))
      (node (ref "T4") (pin "3") (pinfunction "C_3") (pintype "passive"))
    )
    (net (code "101") (name "Net-(T4-E)") (class "Default")
      (node (ref "R30") (pin "2") (pinfunction "2_2") (pintype "passive"))
      (node (ref "T4") (pin "2") (pinfunction "E_2") (pintype "passive"))
    )
    (net (code "102") (name "Net-(T5-C)") (class "Default")
      (node (ref "N1") (pin "8") (pinfunction "8_8") (pintype "output"))
      (node (ref "T5") (pin "3") (pinfunction "C_3") (pintype "passive"))
    )
    (net (code "103") (name "Net-(T5-E)") (class "Default")
      (node (ref "R31") (pin "2") (pinfunction "2_2") (pintype "passive"))
      (node (ref "T5") (pin "2") (pinfunction "E_2") (pintype "passive"))
    )
    (net (code "104") (name "Net-(T6-C)") (class "Default")
      (node (ref "N1") (pin "6") (pinfunction "6_6") (pintype "output"))
      (node (ref "T6") (pin "3") (pinfunction "C_3") (pintype "passive"))
    )
    (net (code "105") (name "Net-(T6-E)") (class "Default")
      (node (ref "R33") (pin "2") (pinfunction "2_2") (pintype "passive"))
      (node (ref "T6") (pin "2") (pinfunction "E_2") (pintype "passive"))
    )
    (net (code "106") (name "Net-(T7-C)") (class "Default")
      (node (ref "N1") (pin "5") (pinfunction "5_5") (pintype "output"))
      (node (ref "T7") (pin "3") (pinfunction "C_3") (pintype "passive"))
    )
    (net (code "107") (name "Net-(T7-E)") (class "Default")
      (node (ref "R34") (pin "2") (pinfunction "2_2") (pintype "passive"))
      (node (ref "T7") (pin "2") (pinfunction "E_2") (pintype "passive"))
    )
    (net (code "108") (name "Net-(T8-C)") (class "Default")
      (node (ref "N1") (pin "4") (pinfunction "4_4") (pintype "output"))
      (node (ref "T8") (pin "3") (pinfunction "C_3") (pintype "passive"))
    )
    (net (code "109") (name "Net-(T8-E)") (class "Default")
      (node (ref "R35") (pin "2") (pinfunction "2_2") (pintype "passive"))
      (node (ref "T8") (pin "2") (pinfunction "E_2") (pintype "passive"))
    )
    (net (code "110") (name "Net-(T9-C)") (class "Default")
      (node (ref "N1") (pin "3") (pinfunction "3_3") (pintype "output"))
      (node (ref "T9") (pin "3") (pinfunction "C_3") (pintype "passive"))
    )
    (net (code "111") (name "Net-(T9-E)") (class "Default")
      (node (ref "R36") (pin "2") (pinfunction "2_2") (pintype "passive"))
      (node (ref "T9") (pin "2") (pinfunction "E_2") (pintype "passive"))
    )
    (net (code "112") (name "Net-(T10-C)") (class "Default")
      (node (ref "N1") (pin "2") (pinfunction "2_2") (pintype "output"))
      (node (ref "T10") (pin "3") (pinfunction "C_3") (pintype "passive"))
    )
    (net (code "113") (name "Net-(T10-E)") (class "Default")
      (node (ref "R37") (pin "2") (pinfunction "2_2") (pintype "passive"))
      (node (ref "T10") (pin "2") (pinfunction "E_2") (pintype "passive"))
    )
    (net (code "114") (name "Net-(T11-C)") (class "Default")
      (node (ref "N1") (pin "1") (pinfunction "1_1") (pintype "output"))
      (node (ref "T11") (pin "3") (pinfunction "C_3") (pintype "passive"))
    )
    (net (code "115") (name "Net-(T11-E)") (class "Default")
      (node (ref "R38") (pin "2") (pinfunction "2_2") (pintype "passive"))
      (node (ref "T11") (pin "2") (pinfunction "E_2") (pintype "passive"))
    )
    (net (code "116") (name "Net-(T12-C)") (class "Default")
      (node (ref "N4") (pin "9") (pinfunction "9_9") (pintype "output"))
      (node (ref "T12") (pin "3") (pinfunction "C_3") (pintype "passive"))
    )
    (net (code "117") (name "Net-(T12-E)") (class "Default")
      (node (ref "R60") (pin "2") (pinfunction "2_2") (pintype "passive"))
      (node (ref "T12") (pin "2") (pinfunction "E_2") (pintype "passive"))
    )
    (net (code "118") (name "Net-(T13-C)") (class "Default")
      (node (ref "N2") (pin "0") (pinfunction "0_0") (pintype "output"))
      (node (ref "T13") (pin "3") (pinfunction "C_3") (pintype "passive"))
    )
    (net (code "119") (name "Net-(T13-E)") (class "Default")
      (node (ref "R39") (pin "2") (pinfunction "2_2") (pintype "passive"))
      (node (ref "T13") (pin "2") (pinfunction "E_2") (pintype "passive"))
    )
    (net (code "120") (name "Net-(T14-C)") (class "Default")
      (node (ref "N2") (pin "9") (pinfunction "9_9") (pintype "output"))
      (node (ref "T14") (pin "3") (pinfunction "C_3") (pintype "passive"))
    )
    (net (code "121") (name "Net-(T14-E)") (class "Default")
      (node (ref "R40") (pin "2") (pinfunction "2_2") (pintype "passive"))
      (node (ref "T14") (pin "2") (pinfunction "E_2") (pintype "passive"))
    )
    (net (code "122") (name "Net-(T15-C)") (class "Default")
      (node (ref "N2") (pin "8") (pinfunction "8_8") (pintype "output"))
      (node (ref "T15") (pin "3") (pinfunction "C_3") (pintype "passive"))
    )
    (net (code "123") (name "Net-(T15-E)") (class "Default")
      (node (ref "R41") (pin "2") (pinfunction "2_2") (pintype "passive"))
      (node (ref "T15") (pin "2") (pinfunction "E_2") (pintype "passive"))
    )
    (net (code "124") (name "Net-(T16-C)") (class "Default")
      (node (ref "N2") (pin "7") (pinfunction "7_7") (pintype "output"))
      (node (ref "T16") (pin "3") (pinfunction "C_3") (pintype "passive"))
    )
    (net (code "125") (name "Net-(T16-E)") (class "Default")
      (node (ref "R42") (pin "2") (pinfunction "2_2") (pintype "passive"))
      (node (ref "T16") (pin "2") (pinfunction "E_2") (pintype "passive"))
    )
    (net (code "126") (name "Net-(T17-C)") (class "Default")
      (node (ref "N2") (pin "6") (pinfunction "6_6") (pintype "output"))
      (node (ref "T17") (pin "3") (pinfunction "C_3") (pintype "passive"))
    )
    (net (code "127") (name "Net-(T17-E)") (class "Default")
      (node (ref "R43") (pin "2") (pinfunction "2_2") (pintype "passive"))
      (node (ref "T17") (pin "2") (pinfunction "E_2") (pintype "passive"))
    )
    (net (code "128") (name "Net-(T18-C)") (class "Default")
      (node (ref "N2") (pin "5") (pinfunction "5_5") (pintype "output"))
      (node (ref "T18") (pin "3") (pinfunction "C_3") (pintype "passive"))
    )
    (net (code "129") (name "Net-(T18-E)") (class "Default")
      (node (ref "R44") (pin "2") (pinfunction "2_2") (pintype "passive"))
      (node (ref "T18") (pin "2") (pinfunction "E_2") (pintype "passive"))
    )
    (net (code "130") (name "Net-(T19-C)") (class "Default")
      (node (ref "N2") (pin "4") (pinfunction "4_4") (pintype "output"))
      (node (ref "T19") (pin "3") (pinfunction "C_3") (pintype "passive"))
    )
    (net (code "131") (name "Net-(T19-E)") (class "Default")
      (node (ref "R45") (pin "2") (pinfunction "2_2") (pintype "passive"))
      (node (ref "T19") (pin "2") (pinfunction "E_2") (pintype "passive"))
    )
    (net (code "132") (name "Net-(T20-C)") (class "Default")
      (node (ref "N2") (pin "3") (pinfunction "3_3") (pintype "output"))
      (node (ref "T20") (pin "3") (pinfunction "C_3") (pintype "passive"))
    )
    (net (code "133") (name "Net-(T20-E)") (class "Default")
      (node (ref "R46") (pin "2") (pinfunction "2_2") (pintype "passive"))
      (node (ref "T20") (pin "2") (pinfunction "E_2") (pintype "passive"))
    )
    (net (code "134") (name "Net-(T21-C)") (class "Default")
      (node (ref "N2") (pin "2") (pinfunction "2_2") (pintype "output"))
      (node (ref "T21") (pin "3") (pinfunction "C_3") (pintype "passive"))
    )
    (net (code "135") (name "Net-(T21-E)") (class "Default")
      (node (ref "R47") (pin "2") (pinfunction "2_2") (pintype "passive"))
      (node (ref "T21") (pin "2") (pinfunction "E_2") (pintype "passive"))
    )
    (net (code "136") (name "Net-(T22-C)") (class "Default")
      (node (ref "N2") (pin "1") (pinfunction "1_1") (pintype "output"))
      (node (ref "T22") (pin "3") (pinfunction "C_3") (pintype "passive"))
    )
    (net (code "137") (name "Net-(T22-E)") (class "Default")
      (node (ref "R48") (pin "2") (pinfunction "2_2") (pintype "passive"))
      (node (ref "T22") (pin "2") (pinfunction "E_2") (pintype "passive"))
    )
    (net (code "138") (name "Net-(T23-C)") (class "Default")
      (node (ref "N3") (pin "0") (pinfunction "0_0") (pintype "output"))
      (node (ref "T23") (pin "3") (pinfunction "C_3") (pintype "passive"))
    )
    (net (code "139") (name "Net-(T23-E)") (class "Default")
      (node (ref "R49") (pin "2") (pinfunction "2_2") (pintype "passive"))
      (node (ref "T23") (pin "2") (pinfunction "E_2") (pintype "passive"))
    )
    (net (code "140") (name "Net-(T24-C)") (class "Default")
      (node (ref "N3") (pin "9") (pinfunction "9_9") (pintype "output"))
      (node (ref "T24") (pin "3") (pinfunction "C_3") (pintype "passive"))
    )
    (net (code "141") (name "Net-(T24-E)") (class "Default")
      (node (ref "R50") (pin "2") (pinfunction "2_2") (pintype "passive"))
      (node (ref "T24") (pin "2") (pinfunction "E_2") (pintype "passive"))
    )
    (net (code "142") (name "Net-(T25-C)") (class "Default")
      (node (ref "N3") (pin "8") (pinfunction "8_8") (pintype "output"))
      (node (ref "T25") (pin "3") (pinfunction "C_3") (pintype "passive"))
    )
    (net (code "143") (name "Net-(T25-E)") (class "Default")
      (node (ref "R51") (pin "2") (pinfunction "2_2") (pintype "passive"))
      (node (ref "T25") (pin "2") (pinfunction "E_2") (pintype "passive"))
    )
    (net (code "144") (name "Net-(T26-C)") (class "Default")
      (node (ref "N3") (pin "7") (pinfunction "7_7") (pintype "output"))
      (node (ref "T26") (pin "3") (pinfunction "C_3") (pintype "passive"))
    )
    (net (code "145") (name "Net-(T26-E)") (class "Default")
      (node (ref "R52") (pin "2") (pinfunction "2_2") (pintype "passive"))
      (node (ref "T26") (pin "2") (pinfunction "E_2") (pintype "passive"))
    )
    (net (code "146") (name "Net-(T27-C)") (class "Default")
      (node (ref "N3") (pin "6") (pinfunction "6_6") (pintype "output"))
      (node (ref "T27") (pin "3") (pinfunction "C_3") (pintype "passive"))
    )
    (net (code "147") (name "Net-(T27-E)") (class "Default")
      (node (ref "R53") (pin "2") (pinfunction "2_2") (pintype "passive"))
      (node (ref "T27") (pin "2") (pinfunction "E_2") (pintype "passive"))
    )
    (net (code "148") (name "Net-(T28-C)") (class "Default")
      (node (ref "N3") (pin "5") (pinfunction "5_5") (pintype "output"))
      (node (ref "T28") (pin "3") (pinfunction "C_3") (pintype "passive"))
    )
    (net (code "149") (name "Net-(T28-E)") (class "Default")
      (node (ref "R54") (pin "2") (pinfunction "2_2") (pintype "passive"))
      (node (ref "T28") (pin "2") (pinfunction "E_2") (pintype "passive"))
    )
    (net (code "150") (name "Net-(T29-C)") (class "Default")
      (node (ref "N3") (pin "4") (pinfunction "4_4") (pintype "output"))
      (node (ref "T29") (pin "3") (pinfunction "C_3") (pintype "passive"))
    )
    (net (code "151") (name "Net-(T29-E)") (class "Default")
      (node (ref "R55") (pin "2") (pinfunction "2_2") (pintype "passive"))
      (node (ref "T29") (pin "2") (pinfunction "E_2") (pintype "passive"))
    )
    (net (code "152") (name "Net-(T30-C)") (class "Default")
      (node (ref "N3") (pin "3") (pinfunction "3_3") (pintype "output"))
      (node (ref "T30") (pin "3") (pinfunction "C_3") (pintype "passive"))
    )
    (net (code "153") (name "Net-(T30-E)") (class "Default")
      (node (ref "R56") (pin "2") (pinfunction "2_2") (pintype "passive"))
      (node (ref "T30") (pin "2") (pinfunction "E_2") (pintype "passive"))
    )
    (net (code "154") (name "Net-(T31-C)") (class "Default")
      (node (ref "N3") (pin "2") (pinfunction "2_2") (pintype "output"))
      (node (ref "T31") (pin "3") (pinfunction "C_3") (pintype "passive"))
    )
    (net (code "155") (name "Net-(T31-E)") (class "Default")
      (node (ref "R57") (pin "2") (pinfunction "2_2") (pintype "passive"))
      (node (ref "T31") (pin "2") (pinfunction "E_2") (pintype "passive"))
    )
    (net (code "156") (name "Net-(T32-C)") (class "Default")
      (node (ref "N3") (pin "1") (pinfunction "1_1") (pintype "output"))
      (node (ref "T32") (pin "3") (pinfunction "C_3") (pintype "passive"))
    )
    (net (code "157") (name "Net-(T32-E)") (class "Default")
      (node (ref "R58") (pin "2") (pinfunction "2_2") (pintype "passive"))
      (node (ref "T32") (pin "2") (pinfunction "E_2") (pintype "passive"))
    )
    (net (code "158") (name "Net-(T33-C)") (class "Default")
      (node (ref "N4") (pin "8") (pinfunction "8_8") (pintype "output"))
      (node (ref "T33") (pin "3") (pinfunction "C_3") (pintype "passive"))
    )
    (net (code "159") (name "Net-(T33-E)") (class "Default")
      (node (ref "R61") (pin "2") (pinfunction "2_2") (pintype "passive"))
      (node (ref "T33") (pin "2") (pinfunction "E_2") (pintype "passive"))
    )
    (net (code "160") (name "Net-(T34-C)") (class "Default")
      (node (ref "N4") (pin "7") (pinfunction "7_7") (pintype "output"))
      (node (ref "T34") (pin "3") (pinfunction "C_3") (pintype "passive"))
    )
    (net (code "161") (name "Net-(T34-E)") (class "Default")
      (node (ref "R62") (pin "2") (pinfunction "2_2") (pintype "passive"))
      (node (ref "T34") (pin "2") (pinfunction "E_2") (pintype "passive"))
    )
    (net (code "162") (name "Net-(T35-C)") (class "Default")
      (node (ref "N4") (pin "6") (pinfunction "6_6") (pintype "output"))
      (node (ref "T35") (pin "3") (pinfunction "C_3") (pintype "passive"))
    )
    (net (code "163") (name "Net-(T35-E)") (class "Default")
      (node (ref "R63") (pin "2") (pinfunction "2_2") (pintype "passive"))
      (node (ref "T35") (pin "2") (pinfunction "E_2") (pintype "passive"))
    )
    (net (code "164") (name "Net-(T36-C)") (class "Default")
      (node (ref "N4") (pin "5") (pinfunction "5_5") (pintype "output"))
      (node (ref "T36") (pin "3") (pinfunction "C_3") (pintype "passive"))
    )
    (net (code "165") (name "Net-(T36-E)") (class "Default")
      (node (ref "R64") (pin "2") (pinfunction "2_2") (pintype "passive"))
      (node (ref "T36") (pin "2") (pinfunction "E_2") (pintype "passive"))
    )
    (net (code "166") (name "Net-(T37-C)") (class "Default")
      (node (ref "N4") (pin "4") (pinfunction "4_4") (pintype "output"))
      (node (ref "T37") (pin "3") (pinfunction "C_3") (pintype "passive"))
    )
    (net (code "167") (name "Net-(T37-E)") (class "Default")
      (node (ref "R65") (pin "2") (pinfunction "2_2") (pintype "passive"))
      (node (ref "T37") (pin "2") (pinfunction "E_2") (pintype "passive"))
    )
    (net (code "168") (name "Net-(T38-C)") (class "Default")
      (node (ref "N4") (pin "3") (pinfunction "3_3") (pintype "output"))
      (node (ref "T38") (pin "3") (pinfunction "C_3") (pintype "passive"))
    )
    (net (code "169") (name "Net-(T38-E)") (class "Default")
      (node (ref "R66") (pin "2") (pinfunction "2_2") (pintype "passive"))
      (node (ref "T38") (pin "2") (pinfunction "E_2") (pintype "passive"))
    )
    (net (code "170") (name "Net-(T39-C)") (class "Default")
      (node (ref "N4") (pin "2") (pinfunction "2_2") (pintype "output"))
      (node (ref "T39") (pin "3") (pinfunction "C_3") (pintype "passive"))
    )
    (net (code "171") (name "Net-(T39-E)") (class "Default")
      (node (ref "R67") (pin "2") (pinfunction "2_2") (pintype "passive"))
      (node (ref "T39") (pin "2") (pinfunction "E_2") (pintype "passive"))
    )
    (net (code "172") (name "Net-(T40-C)") (class "Default")
      (node (ref "N4") (pin "1") (pinfunction "1_1") (pintype "output"))
      (node (ref "T40") (pin "3") (pinfunction "C_3") (pintype "passive"))
    )
    (net (code "173") (name "Net-(T40-E)") (class "Default")
      (node (ref "R68") (pin "2") (pinfunction "2_2") (pintype "passive"))
      (node (ref "T40") (pin "2") (pinfunction "E_2") (pintype "passive"))
    )
    (net (code "174") (name "Net-(T41-B)") (class "Default")
      (node (ref "T41") (pin "1") (pinfunction "B_1") (pintype "passive"))
      (node (ref "U8") (pin "19") (pinfunction "PWM15_19") (pintype "output"))
    )
    (net (code "175") (name "Net-(T41-C)") (class "Default")
      (node (ref "J7") (pin "2") (pinfunction "2_2") (pintype "passive"))
      (node (ref "T41") (pin "3") (pinfunction "C_3") (pintype "passive"))
    )
    (net (code "176") (name "Net-(T41-E)") (class "Default")
      (node (ref "R69") (pin "2") (pinfunction "2_2") (pintype "passive"))
      (node (ref "T41") (pin "2") (pinfunction "E_2") (pintype "passive"))
    )
    (net (code "177") (name "Net-(U2-LX)") (class "Default")
      (node (ref "L3") (pin "2") (pinfunction "2_2") (pintype "passive"))
      (node (ref "U2") (pin "5") (pinfunction "LX_5") (pintype "power_in"))
    )
    (net (code "178") (name "Net-(U3-FBX)") (class "Default")
      (node (ref "C19") (pin "1") (pinfunction "1_1") (pintype "passive"))
      (node (ref "R10") (pin "1") (pinfunction "1_1") (pintype "passive"))
      (node (ref "R11") (pin "2") (pinfunction "2_2") (pintype "passive"))
      (node (ref "R14") (pin "2") (pinfunction "2_2") (pintype "passive"))
      (node (ref "U3") (pin "2") (pinfunction "FBX_2") (pintype "input"))
    )
    (net (code "179") (name "Net-(U3-GATE)") (class "Default")
      (node (ref "R7") (pin "1") (pinfunction "1_1") (pintype "passive"))
      (node (ref "U3") (pin "7") (pinfunction "GATE_7") (pintype "output"))
    )
    (net (code "180") (name "Net-(U3-INTVCC)") (class "Default")
      (node (ref "C11") (pin "1") (pinfunction "1_1") (pintype "passive"))
      (node (ref "C14") (pin "1") (pinfunction "1_1") (pintype "passive"))
      (node (ref "C15") (pin "1") (pinfunction "1_1") (pintype "passive"))
      (node (ref "C17") (pin "1") (pinfunction "1_1") (pintype "passive"))
      (node (ref "C18") (pin "1") (pinfunction "1_1") (pintype "passive"))
      (node (ref "C20") (pin "1") (pinfunction "1_1") (pintype "passive"))
      (node (ref "L4") (pin "5") (pinfunction "P1_5") (pintype "passive"))
      (node (ref "L4") (pin "6") (pinfunction "P1_6") (pintype "passive"))
      (node (ref "R15") (pin "2") (pinfunction "2_2") (pintype "passive"))
      (node (ref "R6") (pin "2") (pinfunction "2_2") (pintype "passive"))
      (node (ref "U3") (pin "10") (pinfunction "VIN_10") (pintype "power_in"))
      (node (ref "U3") (pin "8") (pinfunction "INTVCC_8") (pintype "power_in"))
      (node (ref "U4") (pin "7") (pinfunction "VOUT_7") (pintype "output"))
      (node (ref "U4") (pin "8") (pinfunction "VOUT_8") (pintype "output"))
    )
    (net (code "181") (name "Net-(U3-RT)") (class "Default")
      (node (ref "R9") (pin "2") (pinfunction "2_2") (pintype "passive"))
      (node (ref "U3") (pin "4") (pinfunction "RT_4") (pintype "output"))
    )
    (net (code "182") (name "Net-(U3-SENSE)") (class "Default")
      (node (ref "C16") (pin "1") (pinfunction "1_1") (pintype "passive"))
      (node (ref "R13") (pin "1") (pinfunction "1_1") (pintype "passive"))
      (node (ref "U3") (pin "6") (pinfunction "SENSE_6") (pintype "input"))
    )
    (net (code "183") (name "Net-(U3-SS)") (class "Default")
      (node (ref "C13") (pin "1") (pinfunction "1_1") (pintype "passive"))
      (node (ref "U3") (pin "3") (pinfunction "SS_3") (pintype "power_in"))
    )
    (net (code "184") (name "Net-(U3-VC)") (class "Default")
      (node (ref "C10") (pin "1") (pinfunction "1_1") (pintype "passive"))
      (node (ref "R8") (pin "2") (pinfunction "2_2") (pintype "passive"))
      (node (ref "U3") (pin "1") (pinfunction "VC_1") (pintype "power_in"))
    )
    (net (code "185") (name "Net-(U4-CT)") (class "Default")
      (node (ref "C21") (pin "1") (pinfunction "1_1") (pintype "passive"))
      (node (ref "U4") (pin "6") (pinfunction "CT_6") (pintype "output"))
    )
    (net (code "186") (name "Net-(U5-PA11)") (class "Default")
      (node (ref "R25") (pin "1") (pinfunction "1_1") (pintype "passive"))
      (node (ref "U5") (pin "23") (pinfunction "PA11_23") (pintype "bidirectional"))
    )
    (net (code "187") (name "Net-(U5-PA12)") (class "Default")
      (node (ref "R26") (pin "1") (pinfunction "1_1") (pintype "passive"))
      (node (ref "U5") (pin "24") (pinfunction "PA12_24") (pintype "bidirectional"))
    )
    (net (code "188") (name "Net-(U5-PD0{slash}OSCIN)") (class "Default")
      (node (ref "U5") (pin "2") (pinfunction "PD0/OSCIN_2") (pintype "input"))
      (node (ref "Y1") (pin "1") (pinfunction "1_1") (pintype "passive"))
    )
    (net (code "189") (name "Net-(U5-PD1{slash}OSCOUT)") (class "Default")
      (node (ref "U5") (pin "3") (pinfunction "PD1/OSCOUT_3") (pintype "output"))
      (node (ref "Y1") (pin "3") (pinfunction "3_3") (pintype "passive"))
    )
    (net (code "190") (name "Net-(U5-~{RST})") (class "Default")
      (node (ref "C24") (pin "1") (pinfunction "1_1") (pintype "passive"))
      (node (ref "R16") (pin "1") (pinfunction "1_1") (pintype "passive"))
      (node (ref "R17") (pin "2") (pinfunction "2_2") (pintype "passive"))
      (node (ref "U5") (pin "4") (pinfunction "~{RST}_4") (pintype "input"))
    )
    (net (code "191") (name "Net-(U6-VBAT)") (class "Default")
      (node (ref "BT1") (pin "+") (pinfunction "+_+") (pintype "passive"))
      (node (ref "U6") (pin "1") (pinfunction "VBAT_1") (pintype "bidirectional"))
    )
    (net (code "192") (name "RTCCLK") (class "Default")
      (node (ref "U5") (pin "11") (pinfunction "PA4_11") (pintype "bidirectional"))
      (node (ref "U6") (pin "7") (pinfunction "CLKOUT_7") (pintype "bidirectional"))
    )
    (net (code "193") (name "RTC~{INT}") (class "Default")
      (node (ref "R27") (pin "1") (pinfunction "1_1") (pintype "passive"))
      (node (ref "U5") (pin "12") (pinfunction "PA5_12") (pintype "bidirectional"))
      (node (ref "U6") (pin "3") (pinfunction "~{INT}_3") (pintype "bidirectional"))
    )
    (net (code "194") (name "SCL") (class "Default")
      (node (ref "J3") (pin "3") (pinfunction "3_3") (pintype "bidirectional"))
      (node (ref "R18") (pin "1") (pinfunction "1_1") (pintype "passive"))
      (node (ref "U5") (pin "33") (pinfunction "PB6_33") (pintype "bidirectional"))
      (node (ref "U6") (pin "8") (pinfunction "SCL_8") (pintype "bidirectional"))
    )
    (net (code "195") (name "SDA") (class "Default")
      (node (ref "J3") (pin "2") (pinfunction "2_2") (pintype "bidirectional"))
      (node (ref "R19") (pin "1") (pinfunction "1_1") (pintype "passive"))
      (node (ref "U5") (pin "34") (pinfunction "PB7_34") (pintype "bidirectional"))
      (node (ref "U6") (pin "2") (pinfunction "SDA_2") (pintype "bidirectional"))
    )
    (net (code "196") (name "U_SCL") (class "Default")
      (node (ref "J5") (pin "4") (pinfunction "4_4") (pintype "bidirectional"))
      (node (ref "U7") (pin "23") (pinfunction "SCL_23") (pintype "input"))
      (node (ref "U8") (pin "23") (pinfunction "SCL_23") (pintype "input"))
      (node (ref "U9") (pin "23") (pinfunction "SCL_23") (pintype "input"))
    )
    (net (code "197") (name "U_SDA") (class "Default")
      (node (ref "J5") (pin "1") (pinfunction "1_1") (pintype "bidirectional"))
      (node (ref "U7") (pin "24") (pinfunction "SDA_24") (pintype "bidirectional"))
      (node (ref "U8") (pin "24") (pinfunction "SDA_24") (pintype "bidirectional"))
      (node (ref "U9") (pin "24") (pinfunction "SDA_24") (pintype "bidirectional"))
    )
    (net (code "198") (name "U_~{OE}") (class "Default")
      (node (ref "J5") (pin "3") (pinfunction "3_3") (pintype "bidirectional"))
      (node (ref "U7") (pin "20") (pinfunction "~{OE}_20") (pintype "input"))
      (node (ref "U8") (pin "20") (pinfunction "~{OE}_20") (pintype "input"))
      (node (ref "U9") (pin "20") (pinfunction "~{OE}_20") (pintype "input"))
    )
    (net (code "199") (name "V+") (class "Default")
      (node (ref "C30") (pin "1") (pinfunction "1_1") (pintype "passive"))
      (node (ref "C31") (pin "1") (pinfunction "1_1") (pintype "passive"))
      (node (ref "C32") (pin "1") (pinfunction "1_1") (pintype "passive"))
      (node (ref "D5") (pin "1") (pinfunction "+_1") (pintype "passive"))
      (node (ref "D6") (pin "1") (pinfunction "+_1") (pintype "passive"))
      (node (ref "D7") (pin "1") (pinfunction "+_1") (pintype "passive"))
      (node (ref "D8") (pin "1") (pinfunction "+_1") (pintype "passive"))
      (node (ref "J5") (pin "2") (pinfunction "2_2") (pintype "bidirectional"))
      (node (ref "U7") (pin "25") (pinfunction "VDD_25") (pintype "power_in"))
      (node (ref "U8") (pin "25") (pinfunction "VDD_25") (pintype "power_in"))
      (node (ref "U8") (pin "26") (pinfunction "A0_26") (pintype "input"))
      (node (ref "U9") (pin "25") (pinfunction "VDD_25") (pintype "power_in"))
      (node (ref "U9") (pin "27") (pinfunction "A1_27") (pintype "input"))
    )
    (net (code "200") (name "unconnected-(H1-MOUNT-PadB2,8)") (class "Default")
      (node (ref "H1") (pin "B2,8") (pinfunction "MOUNT_B2,8") (pintype "passive"))
    )
    (net (code "201") (name "unconnected-(H2-MOUNT-PadB2,8)") (class "Default")
      (node (ref "H2") (pin "B2,8") (pinfunction "MOUNT_B2,8") (pintype "passive"))
    )
    (net (code "202") (name "unconnected-(H3-MOUNT-PadB2,8)") (class "Default")
      (node (ref "H3") (pin "B2,8") (pinfunction "MOUNT_B2,8") (pintype "passive"))
    )
    (net (code "203") (name "unconnected-(H4-MOUNT-PadB2,8)") (class "Default")
      (node (ref "H4") (pin "B2,8") (pinfunction "MOUNT_B2,8") (pintype "passive"))
    )
    (net (code "204") (name "unconnected-(H5-MOUNT-PadB2,8)") (class "Default")
      (node (ref "H5") (pin "B2,8") (pinfunction "MOUNT_B2,8") (pintype "passive"))
    )
    (net (code "205") (name "unconnected-(H6-MOUNT-PadB2,8)") (class "Default")
      (node (ref "H6") (pin "B2,8") (pinfunction "MOUNT_B2,8") (pintype "passive"))
    )
    (net (code "206") (name "unconnected-(H7-MOUNT-PadB2,8)") (class "Default")
      (node (ref "H7") (pin "B2,8") (pinfunction "MOUNT_B2,8") (pintype "passive"))
    )
    (net (code "207") (name "unconnected-(H8-MOUNT-PadB2,8)") (class "Default")
      (node (ref "H8") (pin "B2,8") (pinfunction "MOUNT_B2,8") (pintype "passive"))
    )
    (net (code "208") (name "unconnected-(J1-SBU1-PadA8)") (class "Default")
      (node (ref "J1") (pin "A8") (pinfunction "SBU1_A8") (pintype "bidirectional"))
    )
    (net (code "209") (name "unconnected-(J1-SBU2-PadB8)") (class "Default")
      (node (ref "J1") (pin "B8") (pinfunction "SBU2_B8") (pintype "bidirectional"))
    )
    (net (code "210") (name "unconnected-(J2-Pad3)") (class "Default")
      (node (ref "J2") (pin "3") (pinfunction "3_3") (pintype "bidirectional"))
    )
    (net (code "211") (name "unconnected-(J2-Pad4)") (class "Default")
      (node (ref "J2") (pin "4") (pinfunction "4_4") (pintype "bidirectional"))
    )
    (net (code "212") (name "unconnected-(J4-Pad3)") (class "Default")
      (node (ref "J4") (pin "3") (pinfunction "3_3") (pintype "bidirectional"))
    )
    (net (code "213") (name "unconnected-(J4-Pad4)") (class "Default")
      (node (ref "J4") (pin "4") (pinfunction "4_4") (pintype "bidirectional"))
    )
    (net (code "214") (name "unconnected-(J6-Pad3)") (class "Default")
      (node (ref "J6") (pin "3") (pinfunction "3_3") (pintype "passive"))
    )
    (net (code "215") (name "unconnected-(J6-Pad4)") (class "Default")
      (node (ref "J6") (pin "4") (pinfunction "4_4") (pintype "passive"))
    )
    (net (code "216") (name "unconnected-(J6-Pad5)") (class "Default")
      (node (ref "J6") (pin "5") (pinfunction "5_5") (pintype "passive"))
    )
    (net (code "217") (name "unconnected-(U5-PA8-Pad20)") (class "Default")
      (node (ref "U5") (pin "20") (pinfunction "PA8_20") (pintype "bidirectional"))
    )
    (net (code "218") (name "unconnected-(U5-PA9-Pad21)") (class "Default")
      (node (ref "U5") (pin "21") (pinfunction "PA9_21") (pintype "bidirectional"))
    )
    (net (code "219") (name "unconnected-(U5-PA10-Pad22)") (class "Default")
      (node (ref "U5") (pin "22") (pinfunction "PA10_22") (pintype "bidirectional"))
    )
    (net (code "220") (name "unconnected-(U6-EVI-Pad4)") (class "Default")
      (node (ref "U6") (pin "4") (pinfunction "EVI_4") (pintype "bidirectional"))
    )
    (net (code "221") (name "unconnected-(U7-PWM5-Pad8)") (class "Default")
      (node (ref "U7") (pin "8") (pinfunction "PWM5_8") (pintype "output"))
    )
    (net (code "222") (name "~{OE}") (class "Default")
      (node (ref "J3") (pin "4") (pinfunction "4_4") (pintype "bidirectional"))
      (node (ref "R28") (pin "1") (pinfunction "1_1") (pintype "passive"))
      (node (ref "U5") (pin "32") (pinfunction "PB5_32") (pintype "bidirectional"))
    )
  )
)
